# CMOSArray.net
KiCad netlist of a schematic drawn in EAGLE
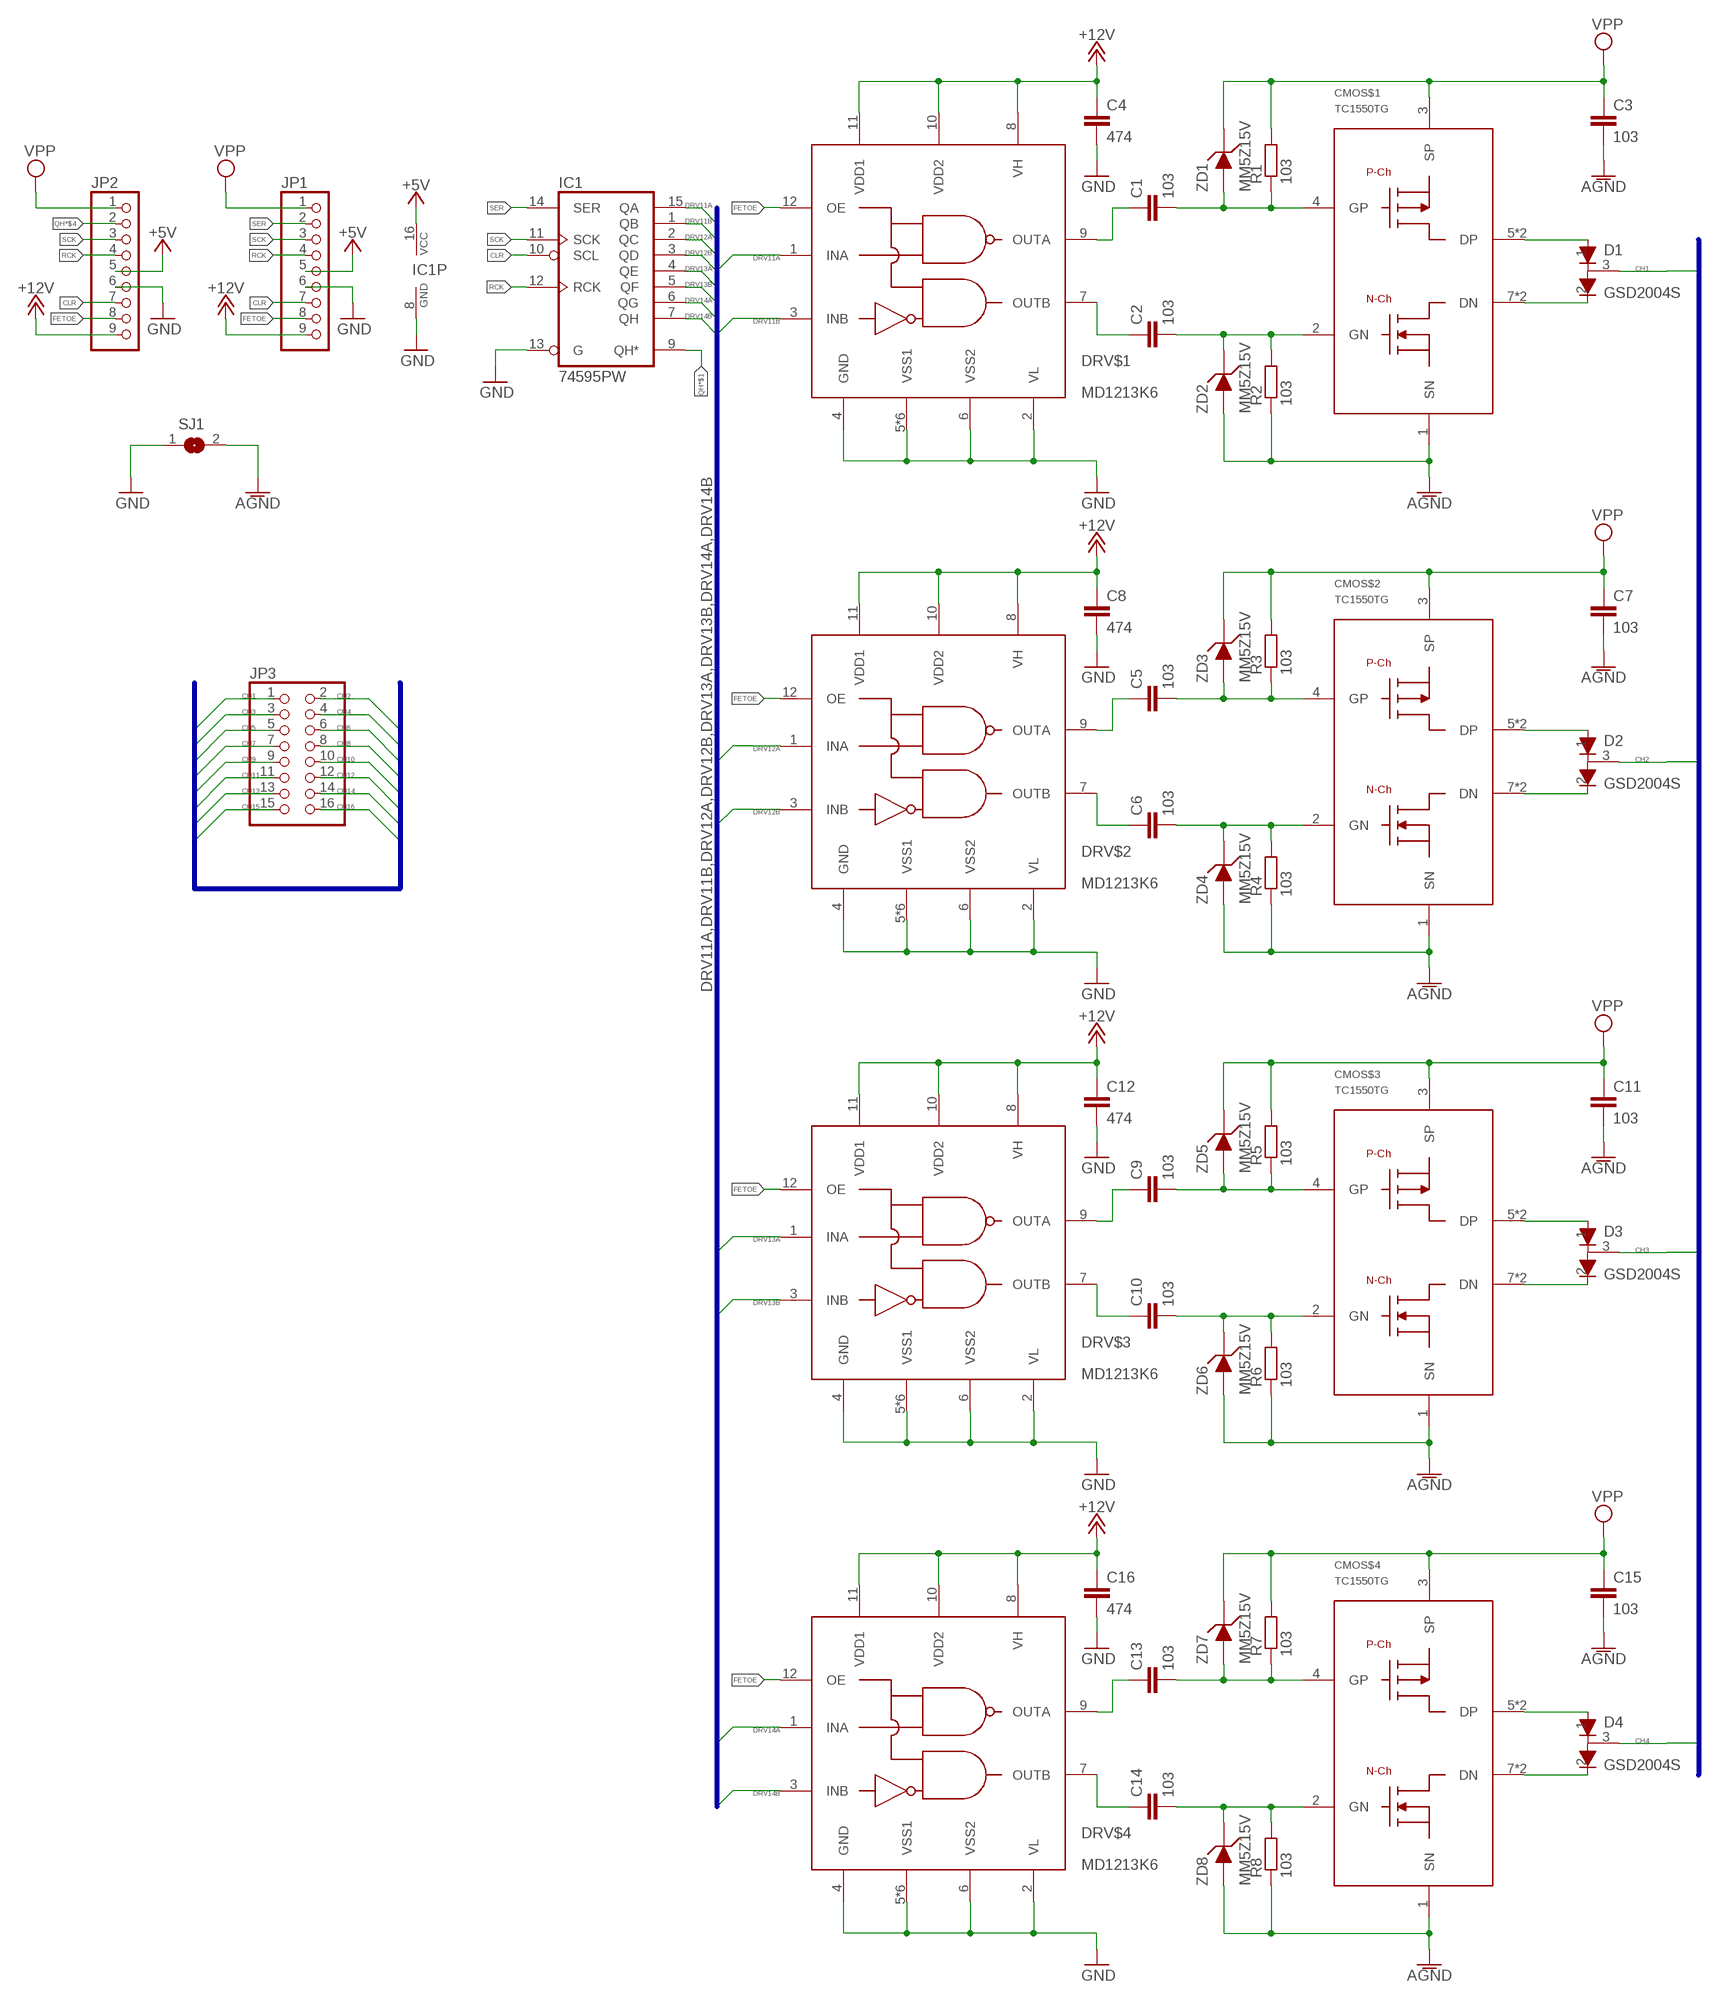
[diagram p0: schematic, sheet 1, part 1 of 3]
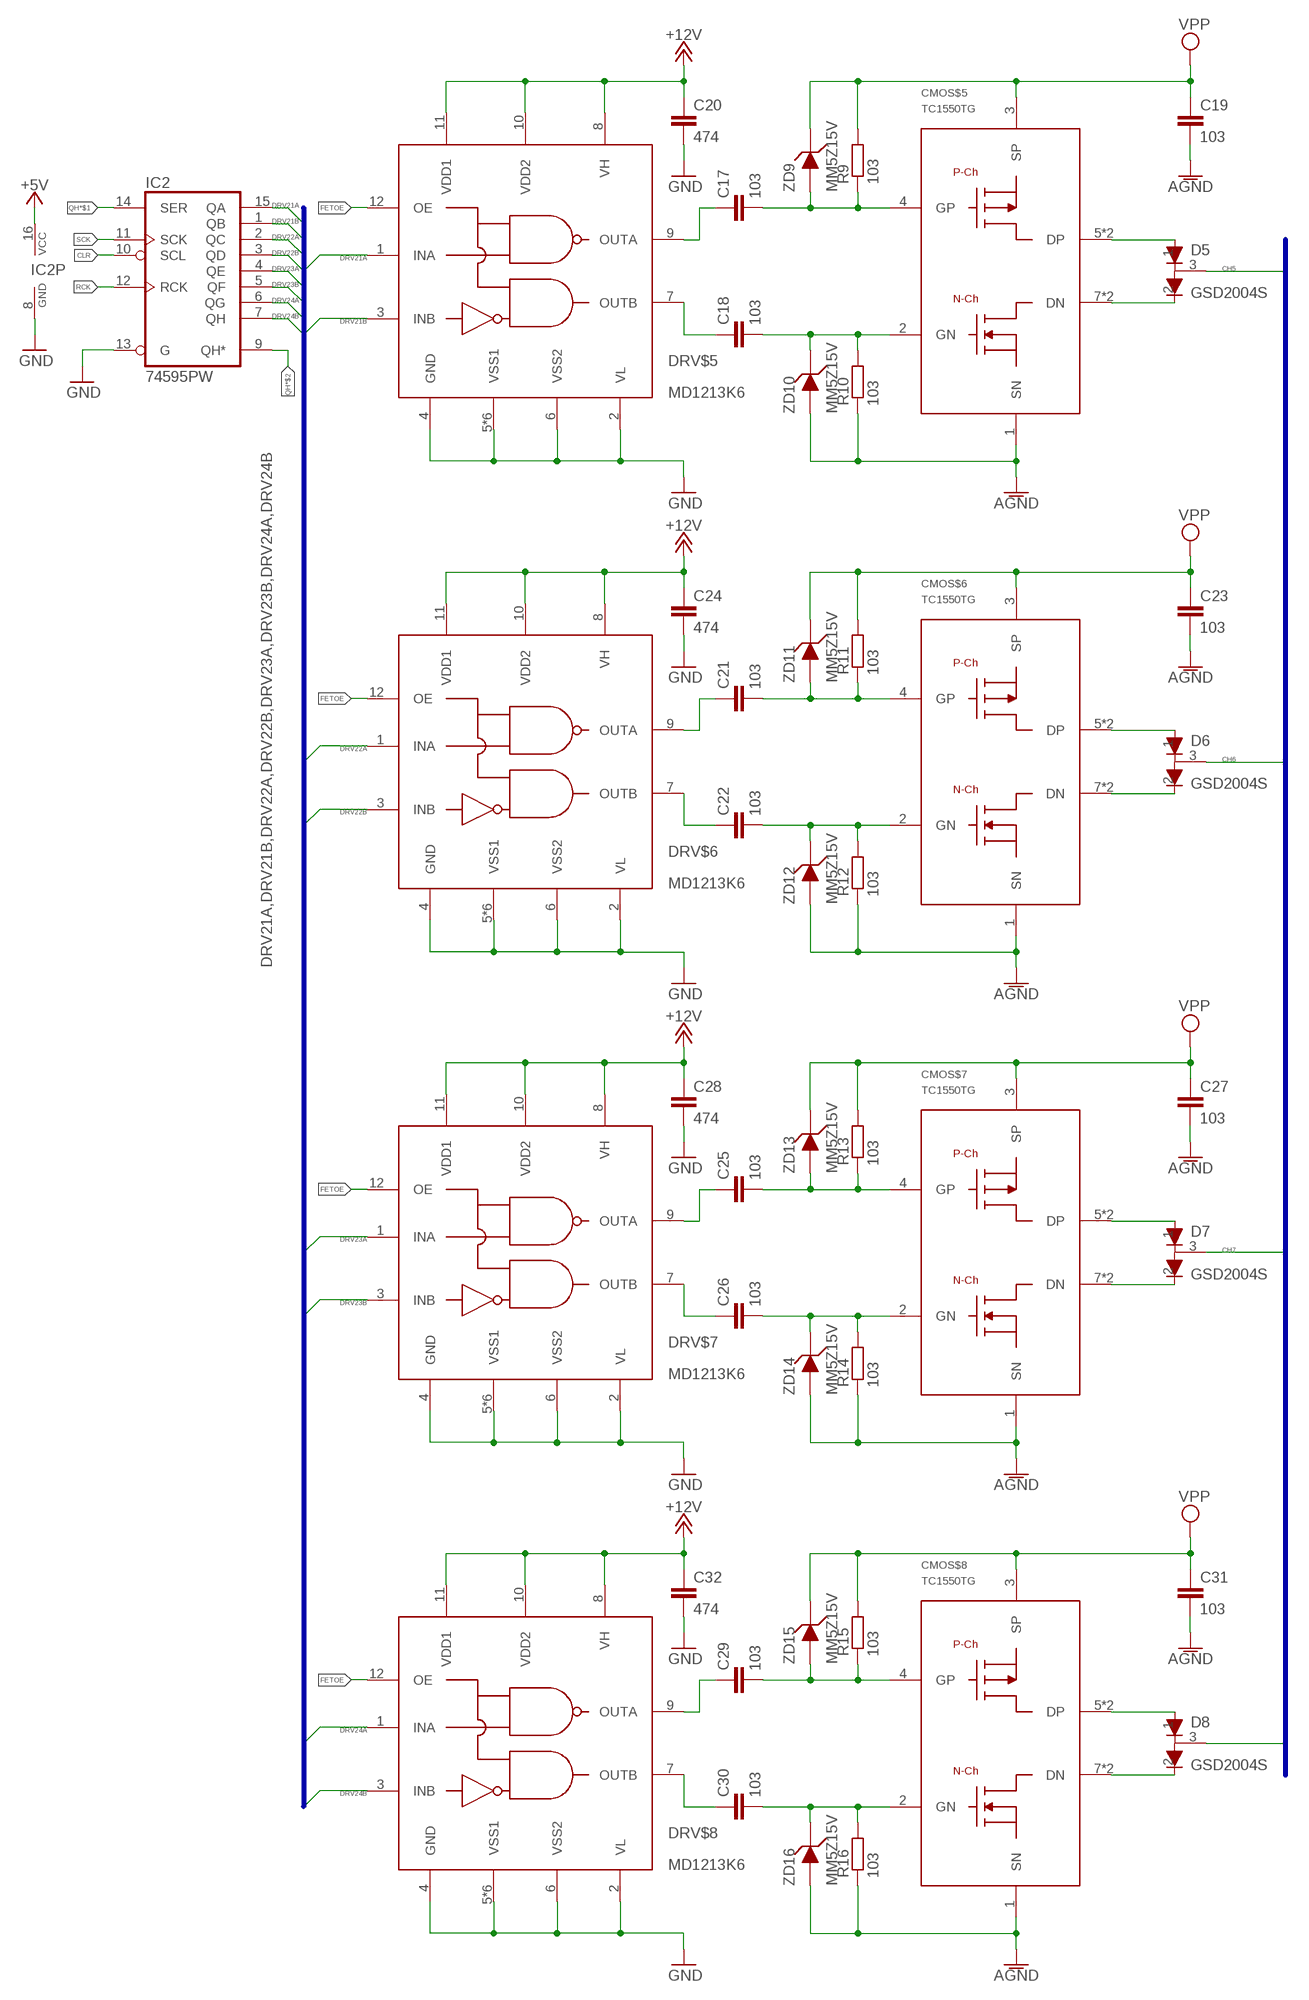
[diagram p1: schematic, sheet 1, part 2 of 3]
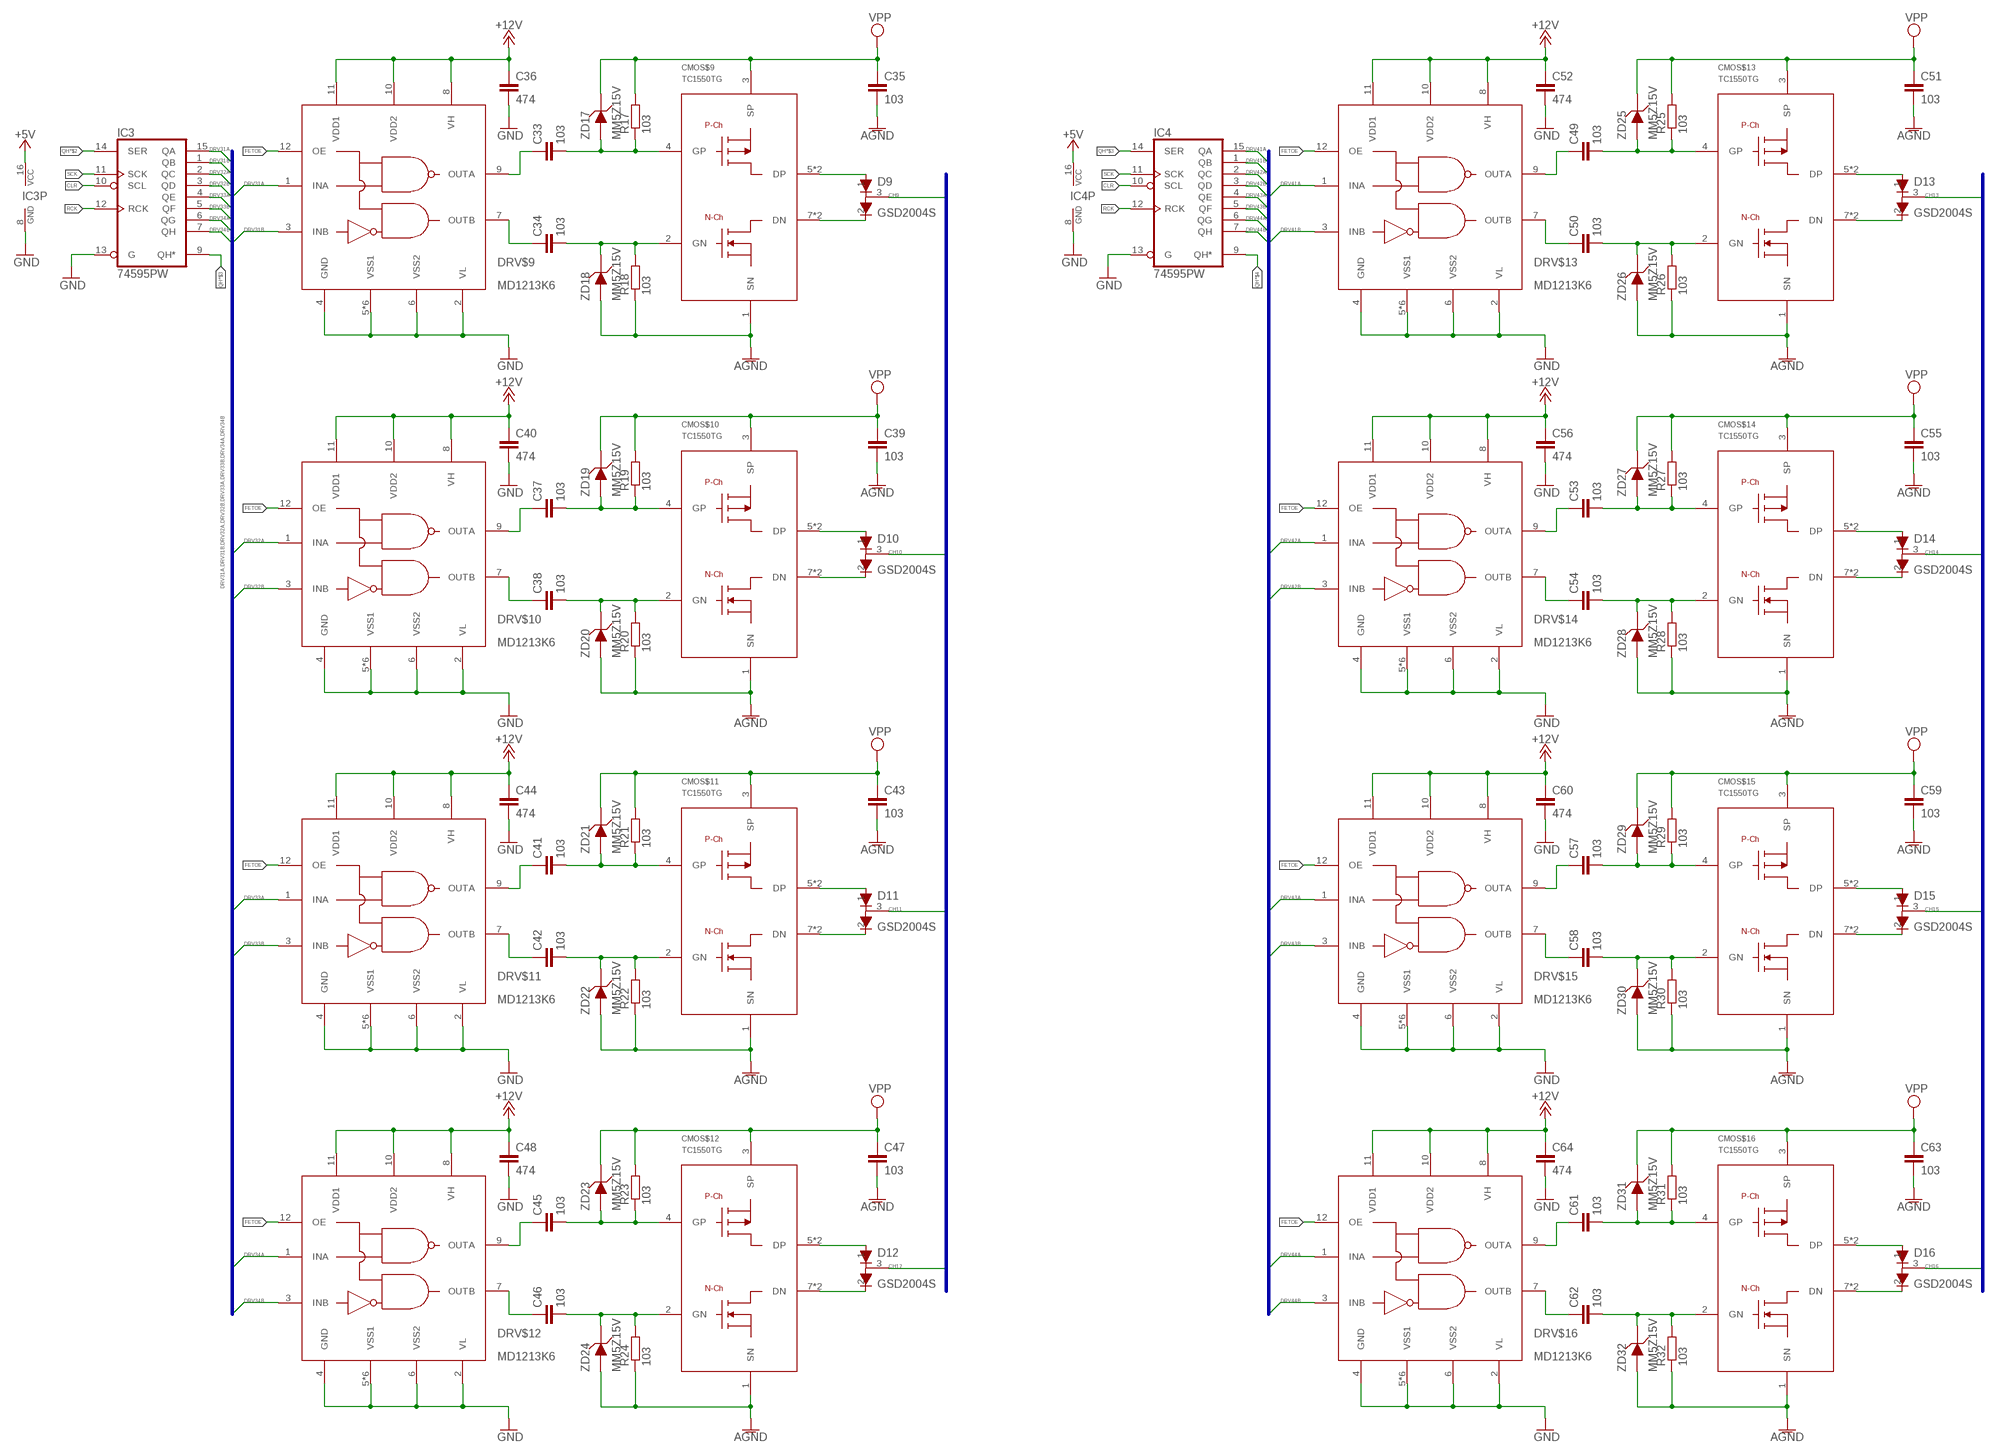
[diagram p2: schematic, sheet 1, part 3 of 3]

(export (version "E")
  (design (tool "Eeschema 10.0.6"))
  (components
    (comp (ref "C1")
      (value "103")
      (footprint "eagle-import:C3216")
      (libsource (lib "eagle-import") (part "C-EUC3216"))
    )
    (comp (ref "C2")
      (value "103")
      (footprint "eagle-import:C3216")
      (libsource (lib "eagle-import") (part "C-EUC3216"))
    )
    (comp (ref "C3")
      (value "103")
      (footprint "eagle-import:C3216")
      (libsource (lib "eagle-import") (part "C-EUC3216"))
    )
    (comp (ref "C4")
      (value "474")
      (footprint "eagle-import:C0402")
      (libsource (lib "eagle-import") (part "C-EUC0402"))
    )
    (comp (ref "C5")
      (value "103")
      (footprint "eagle-import:C3216")
      (libsource (lib "eagle-import") (part "C-EUC3216"))
    )
    (comp (ref "C6")
      (value "103")
      (footprint "eagle-import:C3216")
      (libsource (lib "eagle-import") (part "C-EUC3216"))
    )
    (comp (ref "C7")
      (value "103")
      (footprint "eagle-import:C3216")
      (libsource (lib "eagle-import") (part "C-EUC3216"))
    )
    (comp (ref "C8")
      (value "474")
      (footprint "eagle-import:C0402")
      (libsource (lib "eagle-import") (part "C-EUC0402"))
    )
    (comp (ref "C9")
      (value "103")
      (footprint "eagle-import:C3216")
      (libsource (lib "eagle-import") (part "C-EUC3216"))
    )
    (comp (ref "C10")
      (value "103")
      (footprint "eagle-import:C3216")
      (libsource (lib "eagle-import") (part "C-EUC3216"))
    )
    (comp (ref "C11")
      (value "103")
      (footprint "eagle-import:C3216")
      (libsource (lib "eagle-import") (part "C-EUC3216"))
    )
    (comp (ref "C12")
      (value "474")
      (footprint "eagle-import:C0402")
      (libsource (lib "eagle-import") (part "C-EUC0402"))
    )
    (comp (ref "C13")
      (value "103")
      (footprint "eagle-import:C3216")
      (libsource (lib "eagle-import") (part "C-EUC3216"))
    )
    (comp (ref "C14")
      (value "103")
      (footprint "eagle-import:C3216")
      (libsource (lib "eagle-import") (part "C-EUC3216"))
    )
    (comp (ref "C15")
      (value "103")
      (footprint "eagle-import:C3216")
      (libsource (lib "eagle-import") (part "C-EUC3216"))
    )
    (comp (ref "C16")
      (value "474")
      (footprint "eagle-import:C0402")
      (libsource (lib "eagle-import") (part "C-EUC0402"))
    )
    (comp (ref "C17")
      (value "103")
      (footprint "eagle-import:C3216")
      (libsource (lib "eagle-import") (part "C-EUC3216"))
    )
    (comp (ref "C18")
      (value "103")
      (footprint "eagle-import:C3216")
      (libsource (lib "eagle-import") (part "C-EUC3216"))
    )
    (comp (ref "C19")
      (value "103")
      (footprint "eagle-import:C3216")
      (libsource (lib "eagle-import") (part "C-EUC3216"))
    )
    (comp (ref "C20")
      (value "474")
      (footprint "eagle-import:C0402")
      (libsource (lib "eagle-import") (part "C-EUC0402"))
    )
    (comp (ref "C21")
      (value "103")
      (footprint "eagle-import:C3216")
      (libsource (lib "eagle-import") (part "C-EUC3216"))
    )
    (comp (ref "C22")
      (value "103")
      (footprint "eagle-import:C3216")
      (libsource (lib "eagle-import") (part "C-EUC3216"))
    )
    (comp (ref "C23")
      (value "103")
      (footprint "eagle-import:C3216")
      (libsource (lib "eagle-import") (part "C-EUC3216"))
    )
    (comp (ref "C24")
      (value "474")
      (footprint "eagle-import:C0402")
      (libsource (lib "eagle-import") (part "C-EUC0402"))
    )
    (comp (ref "C25")
      (value "103")
      (footprint "eagle-import:C3216")
      (libsource (lib "eagle-import") (part "C-EUC3216"))
    )
    (comp (ref "C26")
      (value "103")
      (footprint "eagle-import:C3216")
      (libsource (lib "eagle-import") (part "C-EUC3216"))
    )
    (comp (ref "C27")
      (value "103")
      (footprint "eagle-import:C3216")
      (libsource (lib "eagle-import") (part "C-EUC3216"))
    )
    (comp (ref "C28")
      (value "474")
      (footprint "eagle-import:C0402")
      (libsource (lib "eagle-import") (part "C-EUC0402"))
    )
    (comp (ref "C29")
      (value "103")
      (footprint "eagle-import:C3216")
      (libsource (lib "eagle-import") (part "C-EUC3216"))
    )
    (comp (ref "C30")
      (value "103")
      (footprint "eagle-import:C3216")
      (libsource (lib "eagle-import") (part "C-EUC3216"))
    )
    (comp (ref "C31")
      (value "103")
      (footprint "eagle-import:C3216")
      (libsource (lib "eagle-import") (part "C-EUC3216"))
    )
    (comp (ref "C32")
      (value "474")
      (footprint "eagle-import:C0402")
      (libsource (lib "eagle-import") (part "C-EUC0402"))
    )
    (comp (ref "C33")
      (value "103")
      (footprint "eagle-import:C3216")
      (libsource (lib "eagle-import") (part "C-EUC3216"))
    )
    (comp (ref "C34")
      (value "103")
      (footprint "eagle-import:C3216")
      (libsource (lib "eagle-import") (part "C-EUC3216"))
    )
    (comp (ref "C35")
      (value "103")
      (footprint "eagle-import:C3216")
      (libsource (lib "eagle-import") (part "C-EUC3216"))
    )
    (comp (ref "C36")
      (value "474")
      (footprint "eagle-import:C0402")
      (libsource (lib "eagle-import") (part "C-EUC0402"))
    )
    (comp (ref "C37")
      (value "103")
      (footprint "eagle-import:C3216")
      (libsource (lib "eagle-import") (part "C-EUC3216"))
    )
    (comp (ref "C38")
      (value "103")
      (footprint "eagle-import:C3216")
      (libsource (lib "eagle-import") (part "C-EUC3216"))
    )
    (comp (ref "C39")
      (value "103")
      (footprint "eagle-import:C3216")
      (libsource (lib "eagle-import") (part "C-EUC3216"))
    )
    (comp (ref "C40")
      (value "474")
      (footprint "eagle-import:C0402")
      (libsource (lib "eagle-import") (part "C-EUC0402"))
    )
    (comp (ref "C41")
      (value "103")
      (footprint "eagle-import:C3216")
      (libsource (lib "eagle-import") (part "C-EUC3216"))
    )
    (comp (ref "C42")
      (value "103")
      (footprint "eagle-import:C3216")
      (libsource (lib "eagle-import") (part "C-EUC3216"))
    )
    (comp (ref "C43")
      (value "103")
      (footprint "eagle-import:C3216")
      (libsource (lib "eagle-import") (part "C-EUC3216"))
    )
    (comp (ref "C44")
      (value "474")
      (footprint "eagle-import:C0402")
      (libsource (lib "eagle-import") (part "C-EUC0402"))
    )
    (comp (ref "C45")
      (value "103")
      (footprint "eagle-import:C3216")
      (libsource (lib "eagle-import") (part "C-EUC3216"))
    )
    (comp (ref "C46")
      (value "103")
      (footprint "eagle-import:C3216")
      (libsource (lib "eagle-import") (part "C-EUC3216"))
    )
    (comp (ref "C47")
      (value "103")
      (footprint "eagle-import:C3216")
      (libsource (lib "eagle-import") (part "C-EUC3216"))
    )
    (comp (ref "C48")
      (value "474")
      (footprint "eagle-import:C0402")
      (libsource (lib "eagle-import") (part "C-EUC0402"))
    )
    (comp (ref "C49")
      (value "103")
      (footprint "eagle-import:C3216")
      (libsource (lib "eagle-import") (part "C-EUC3216"))
    )
    (comp (ref "C50")
      (value "103")
      (footprint "eagle-import:C3216")
      (libsource (lib "eagle-import") (part "C-EUC3216"))
    )
    (comp (ref "C51")
      (value "103")
      (footprint "eagle-import:C3216")
      (libsource (lib "eagle-import") (part "C-EUC3216"))
    )
    (comp (ref "C52")
      (value "474")
      (footprint "eagle-import:C0402")
      (libsource (lib "eagle-import") (part "C-EUC0402"))
    )
    (comp (ref "C53")
      (value "103")
      (footprint "eagle-import:C3216")
      (libsource (lib "eagle-import") (part "C-EUC3216"))
    )
    (comp (ref "C54")
      (value "103")
      (footprint "eagle-import:C3216")
      (libsource (lib "eagle-import") (part "C-EUC3216"))
    )
    (comp (ref "C55")
      (value "103")
      (footprint "eagle-import:C3216")
      (libsource (lib "eagle-import") (part "C-EUC3216"))
    )
    (comp (ref "C56")
      (value "474")
      (footprint "eagle-import:C0402")
      (libsource (lib "eagle-import") (part "C-EUC0402"))
    )
    (comp (ref "C57")
      (value "103")
      (footprint "eagle-import:C3216")
      (libsource (lib "eagle-import") (part "C-EUC3216"))
    )
    (comp (ref "C58")
      (value "103")
      (footprint "eagle-import:C3216")
      (libsource (lib "eagle-import") (part "C-EUC3216"))
    )
    (comp (ref "C59")
      (value "103")
      (footprint "eagle-import:C3216")
      (libsource (lib "eagle-import") (part "C-EUC3216"))
    )
    (comp (ref "C60")
      (value "474")
      (footprint "eagle-import:C0402")
      (libsource (lib "eagle-import") (part "C-EUC0402"))
    )
    (comp (ref "C61")
      (value "103")
      (footprint "eagle-import:C3216")
      (libsource (lib "eagle-import") (part "C-EUC3216"))
    )
    (comp (ref "C62")
      (value "103")
      (footprint "eagle-import:C3216")
      (libsource (lib "eagle-import") (part "C-EUC3216"))
    )
    (comp (ref "C63")
      (value "103")
      (footprint "eagle-import:C3216")
      (libsource (lib "eagle-import") (part "C-EUC3216"))
    )
    (comp (ref "C64")
      (value "474")
      (footprint "eagle-import:C0402")
      (libsource (lib "eagle-import") (part "C-EUC0402"))
    )
    (comp (ref "CMOS$1")
      (value "TC1550TG")
      (footprint "eagle-import:SOIC-08LG")
      (libsource (lib "eagle-import") (part "TC1550TG"))
    )
    (comp (ref "CMOS$2")
      (value "TC1550TG")
      (footprint "eagle-import:SOIC-08LG")
      (libsource (lib "eagle-import") (part "TC1550TG"))
    )
    (comp (ref "CMOS$3")
      (value "TC1550TG")
      (footprint "eagle-import:SOIC-08LG")
      (libsource (lib "eagle-import") (part "TC1550TG"))
    )
    (comp (ref "CMOS$4")
      (value "TC1550TG")
      (footprint "eagle-import:SOIC-08LG")
      (libsource (lib "eagle-import") (part "TC1550TG"))
    )
    (comp (ref "CMOS$5")
      (value "TC1550TG")
      (footprint "eagle-import:SOIC-08LG")
      (libsource (lib "eagle-import") (part "TC1550TG"))
    )
    (comp (ref "CMOS$6")
      (value "TC1550TG")
      (footprint "eagle-import:SOIC-08LG")
      (libsource (lib "eagle-import") (part "TC1550TG"))
    )
    (comp (ref "CMOS$7")
      (value "TC1550TG")
      (footprint "eagle-import:SOIC-08LG")
      (libsource (lib "eagle-import") (part "TC1550TG"))
    )
    (comp (ref "CMOS$8")
      (value "TC1550TG")
      (footprint "eagle-import:SOIC-08LG")
      (libsource (lib "eagle-import") (part "TC1550TG"))
    )
    (comp (ref "CMOS$9")
      (value "TC1550TG")
      (footprint "eagle-import:SOIC-08LG")
      (libsource (lib "eagle-import") (part "TC1550TG"))
    )
    (comp (ref "CMOS$10")
      (value "TC1550TG")
      (footprint "eagle-import:SOIC-08LG")
      (libsource (lib "eagle-import") (part "TC1550TG"))
    )
    (comp (ref "CMOS$11")
      (value "TC1550TG")
      (footprint "eagle-import:SOIC-08LG")
      (libsource (lib "eagle-import") (part "TC1550TG"))
    )
    (comp (ref "CMOS$12")
      (value "TC1550TG")
      (footprint "eagle-import:SOIC-08LG")
      (libsource (lib "eagle-import") (part "TC1550TG"))
    )
    (comp (ref "CMOS$13")
      (value "TC1550TG")
      (footprint "eagle-import:SOIC-08LG")
      (libsource (lib "eagle-import") (part "TC1550TG"))
    )
    (comp (ref "CMOS$14")
      (value "TC1550TG")
      (footprint "eagle-import:SOIC-08LG")
      (libsource (lib "eagle-import") (part "TC1550TG"))
    )
    (comp (ref "CMOS$15")
      (value "TC1550TG")
      (footprint "eagle-import:SOIC-08LG")
      (libsource (lib "eagle-import") (part "TC1550TG"))
    )
    (comp (ref "CMOS$16")
      (value "TC1550TG")
      (footprint "eagle-import:SOIC-08LG")
      (libsource (lib "eagle-import") (part "TC1550TG"))
    )
    (comp (ref "D1")
      (value "GSD2004S")
      (footprint "eagle-import:SOT23")
      (libsource (lib "eagle-import") (part "GSD2004S"))
    )
    (comp (ref "D2")
      (value "GSD2004S")
      (footprint "eagle-import:SOT23")
      (libsource (lib "eagle-import") (part "GSD2004S"))
    )
    (comp (ref "D3")
      (value "GSD2004S")
      (footprint "eagle-import:SOT23")
      (libsource (lib "eagle-import") (part "GSD2004S"))
    )
    (comp (ref "D4")
      (value "GSD2004S")
      (footprint "eagle-import:SOT23")
      (libsource (lib "eagle-import") (part "GSD2004S"))
    )
    (comp (ref "D5")
      (value "GSD2004S")
      (footprint "eagle-import:SOT23")
      (libsource (lib "eagle-import") (part "GSD2004S"))
    )
    (comp (ref "D6")
      (value "GSD2004S")
      (footprint "eagle-import:SOT23")
      (libsource (lib "eagle-import") (part "GSD2004S"))
    )
    (comp (ref "D7")
      (value "GSD2004S")
      (footprint "eagle-import:SOT23")
      (libsource (lib "eagle-import") (part "GSD2004S"))
    )
    (comp (ref "D8")
      (value "GSD2004S")
      (footprint "eagle-import:SOT23")
      (libsource (lib "eagle-import") (part "GSD2004S"))
    )
    (comp (ref "D9")
      (value "GSD2004S")
      (footprint "eagle-import:SOT23")
      (libsource (lib "eagle-import") (part "GSD2004S"))
    )
    (comp (ref "D10")
      (value "GSD2004S")
      (footprint "eagle-import:SOT23")
      (libsource (lib "eagle-import") (part "GSD2004S"))
    )
    (comp (ref "D11")
      (value "GSD2004S")
      (footprint "eagle-import:SOT23")
      (libsource (lib "eagle-import") (part "GSD2004S"))
    )
    (comp (ref "D12")
      (value "GSD2004S")
      (footprint "eagle-import:SOT23")
      (libsource (lib "eagle-import") (part "GSD2004S"))
    )
    (comp (ref "D13")
      (value "GSD2004S")
      (footprint "eagle-import:SOT23")
      (libsource (lib "eagle-import") (part "GSD2004S"))
    )
    (comp (ref "D14")
      (value "GSD2004S")
      (footprint "eagle-import:SOT23")
      (libsource (lib "eagle-import") (part "GSD2004S"))
    )
    (comp (ref "D15")
      (value "GSD2004S")
      (footprint "eagle-import:SOT23")
      (libsource (lib "eagle-import") (part "GSD2004S"))
    )
    (comp (ref "D16")
      (value "GSD2004S")
      (footprint "eagle-import:SOT23")
      (libsource (lib "eagle-import") (part "GSD2004S"))
    )
    (comp (ref "DRV$1")
      (value "MD1213K6")
      (footprint "eagle-import:QFN12")
      (libsource (lib "eagle-import") (part "MD1213K6"))
    )
    (comp (ref "DRV$2")
      (value "MD1213K6")
      (footprint "eagle-import:QFN12")
      (libsource (lib "eagle-import") (part "MD1213K6"))
    )
    (comp (ref "DRV$3")
      (value "MD1213K6")
      (footprint "eagle-import:QFN12")
      (libsource (lib "eagle-import") (part "MD1213K6"))
    )
    (comp (ref "DRV$4")
      (value "MD1213K6")
      (footprint "eagle-import:QFN12")
      (libsource (lib "eagle-import") (part "MD1213K6"))
    )
    (comp (ref "DRV$5")
      (value "MD1213K6")
      (footprint "eagle-import:QFN12")
      (libsource (lib "eagle-import") (part "MD1213K6"))
    )
    (comp (ref "DRV$6")
      (value "MD1213K6")
      (footprint "eagle-import:QFN12")
      (libsource (lib "eagle-import") (part "MD1213K6"))
    )
    (comp (ref "DRV$7")
      (value "MD1213K6")
      (footprint "eagle-import:QFN12")
      (libsource (lib "eagle-import") (part "MD1213K6"))
    )
    (comp (ref "DRV$8")
      (value "MD1213K6")
      (footprint "eagle-import:QFN12")
      (libsource (lib "eagle-import") (part "MD1213K6"))
    )
    (comp (ref "DRV$9")
      (value "MD1213K6")
      (footprint "eagle-import:QFN12")
      (libsource (lib "eagle-import") (part "MD1213K6"))
    )
    (comp (ref "DRV$10")
      (value "MD1213K6")
      (footprint "eagle-import:QFN12")
      (libsource (lib "eagle-import") (part "MD1213K6"))
    )
    (comp (ref "DRV$11")
      (value "MD1213K6")
      (footprint "eagle-import:QFN12")
      (libsource (lib "eagle-import") (part "MD1213K6"))
    )
    (comp (ref "DRV$12")
      (value "MD1213K6")
      (footprint "eagle-import:QFN12")
      (libsource (lib "eagle-import") (part "MD1213K6"))
    )
    (comp (ref "DRV$13")
      (value "MD1213K6")
      (footprint "eagle-import:QFN12")
      (libsource (lib "eagle-import") (part "MD1213K6"))
    )
    (comp (ref "DRV$14")
      (value "MD1213K6")
      (footprint "eagle-import:QFN12")
      (libsource (lib "eagle-import") (part "MD1213K6"))
    )
    (comp (ref "DRV$15")
      (value "MD1213K6")
      (footprint "eagle-import:QFN12")
      (libsource (lib "eagle-import") (part "MD1213K6"))
    )
    (comp (ref "DRV$16")
      (value "MD1213K6")
      (footprint "eagle-import:QFN12")
      (libsource (lib "eagle-import") (part "MD1213K6"))
    )
    (comp (ref "IC1")
      (value "74595PW")
      (footprint "eagle-import:TTSOP16")
      (libsource (lib "eagle-import") (part "74595PW"))
    )
    (comp (ref "IC2")
      (value "74595PW")
      (footprint "eagle-import:TTSOP16")
      (libsource (lib "eagle-import") (part "74595PW"))
    )
    (comp (ref "IC3")
      (value "74595PW")
      (footprint "eagle-import:TTSOP16")
      (libsource (lib "eagle-import") (part "74595PW"))
    )
    (comp (ref "IC4")
      (value "74595PW")
      (footprint "eagle-import:TTSOP16")
      (libsource (lib "eagle-import") (part "74595PW"))
    )
    (comp (ref "JP1")
      (value "PINHD-1X9")
      (footprint "eagle-import:1X09")
      (libsource (lib "eagle-import") (part "PINHD-1X9"))
    )
    (comp (ref "JP2")
      (value "PINHD-1X9")
      (footprint "eagle-import:1X09")
      (libsource (lib "eagle-import") (part "PINHD-1X9"))
    )
    (comp (ref "JP3")
      (value "PINHD-2X8")
      (footprint "eagle-import:2X08")
      (libsource (lib "eagle-import") (part "PINHD-2X8"))
    )
    (comp (ref "R1")
      (value "103")
      (footprint "eagle-import:R0402")
      (libsource (lib "eagle-import") (part "R-EU_R0402"))
    )
    (comp (ref "R2")
      (value "103")
      (footprint "eagle-import:R0402")
      (libsource (lib "eagle-import") (part "R-EU_R0402"))
    )
    (comp (ref "R3")
      (value "103")
      (footprint "eagle-import:R0402")
      (libsource (lib "eagle-import") (part "R-EU_R0402"))
    )
    (comp (ref "R4")
      (value "103")
      (footprint "eagle-import:R0402")
      (libsource (lib "eagle-import") (part "R-EU_R0402"))
    )
    (comp (ref "R5")
      (value "103")
      (footprint "eagle-import:R0402")
      (libsource (lib "eagle-import") (part "R-EU_R0402"))
    )
    (comp (ref "R6")
      (value "103")
      (footprint "eagle-import:R0402")
      (libsource (lib "eagle-import") (part "R-EU_R0402"))
    )
    (comp (ref "R7")
      (value "103")
      (footprint "eagle-import:R0402")
      (libsource (lib "eagle-import") (part "R-EU_R0402"))
    )
    (comp (ref "R8")
      (value "103")
      (footprint "eagle-import:R0402")
      (libsource (lib "eagle-import") (part "R-EU_R0402"))
    )
    (comp (ref "R9")
      (value "103")
      (footprint "eagle-import:R0402")
      (libsource (lib "eagle-import") (part "R-EU_R0402"))
    )
    (comp (ref "R10")
      (value "103")
      (footprint "eagle-import:R0402")
      (libsource (lib "eagle-import") (part "R-EU_R0402"))
    )
    (comp (ref "R11")
      (value "103")
      (footprint "eagle-import:R0402")
      (libsource (lib "eagle-import") (part "R-EU_R0402"))
    )
    (comp (ref "R12")
      (value "103")
      (footprint "eagle-import:R0402")
      (libsource (lib "eagle-import") (part "R-EU_R0402"))
    )
    (comp (ref "R13")
      (value "103")
      (footprint "eagle-import:R0402")
      (libsource (lib "eagle-import") (part "R-EU_R0402"))
    )
    (comp (ref "R14")
      (value "103")
      (footprint "eagle-import:R0402")
      (libsource (lib "eagle-import") (part "R-EU_R0402"))
    )
    (comp (ref "R15")
      (value "103")
      (footprint "eagle-import:R0402")
      (libsource (lib "eagle-import") (part "R-EU_R0402"))
    )
    (comp (ref "R16")
      (value "103")
      (footprint "eagle-import:R0402")
      (libsource (lib "eagle-import") (part "R-EU_R0402"))
    )
    (comp (ref "R17")
      (value "103")
      (footprint "eagle-import:R0402")
      (libsource (lib "eagle-import") (part "R-EU_R0402"))
    )
    (comp (ref "R18")
      (value "103")
      (footprint "eagle-import:R0402")
      (libsource (lib "eagle-import") (part "R-EU_R0402"))
    )
    (comp (ref "R19")
      (value "103")
      (footprint "eagle-import:R0402")
      (libsource (lib "eagle-import") (part "R-EU_R0402"))
    )
    (comp (ref "R20")
      (value "103")
      (footprint "eagle-import:R0402")
      (libsource (lib "eagle-import") (part "R-EU_R0402"))
    )
    (comp (ref "R21")
      (value "103")
      (footprint "eagle-import:R0402")
      (libsource (lib "eagle-import") (part "R-EU_R0402"))
    )
    (comp (ref "R22")
      (value "103")
      (footprint "eagle-import:R0402")
      (libsource (lib "eagle-import") (part "R-EU_R0402"))
    )
    (comp (ref "R23")
      (value "103")
      (footprint "eagle-import:R0402")
      (libsource (lib "eagle-import") (part "R-EU_R0402"))
    )
    (comp (ref "R24")
      (value "103")
      (footprint "eagle-import:R0402")
      (libsource (lib "eagle-import") (part "R-EU_R0402"))
    )
    (comp (ref "R25")
      (value "103")
      (footprint "eagle-import:R0402")
      (libsource (lib "eagle-import") (part "R-EU_R0402"))
    )
    (comp (ref "R26")
      (value "103")
      (footprint "eagle-import:R0402")
      (libsource (lib "eagle-import") (part "R-EU_R0402"))
    )
    (comp (ref "R27")
      (value "103")
      (footprint "eagle-import:R0402")
      (libsource (lib "eagle-import") (part "R-EU_R0402"))
    )
    (comp (ref "R28")
      (value "103")
      (footprint "eagle-import:R0402")
      (libsource (lib "eagle-import") (part "R-EU_R0402"))
    )
    (comp (ref "R29")
      (value "103")
      (footprint "eagle-import:R0402")
      (libsource (lib "eagle-import") (part "R-EU_R0402"))
    )
    (comp (ref "R30")
      (value "103")
      (footprint "eagle-import:R0402")
      (libsource (lib "eagle-import") (part "R-EU_R0402"))
    )
    (comp (ref "R31")
      (value "103")
      (footprint "eagle-import:R0402")
      (libsource (lib "eagle-import") (part "R-EU_R0402"))
    )
    (comp (ref "R32")
      (value "103")
      (footprint "eagle-import:R0402")
      (libsource (lib "eagle-import") (part "R-EU_R0402"))
    )
    (comp (ref "SJ1") (value "SJ") (footprint "eagle-import:SJ") (libsource (lib "eagle-import") (part "SJ")))
    (comp (ref "ZD1")
      (value "MM5Z15V")
      (footprint "eagle-import:SOD523")
      (libsource (lib "eagle-import") (part "MM5Z15V"))
    )
    (comp (ref "ZD2")
      (value "MM5Z15V")
      (footprint "eagle-import:SOD523")
      (libsource (lib "eagle-import") (part "MM5Z15V"))
    )
    (comp (ref "ZD3")
      (value "MM5Z15V")
      (footprint "eagle-import:SOD523")
      (libsource (lib "eagle-import") (part "MM5Z15V"))
    )
    (comp (ref "ZD4")
      (value "MM5Z15V")
      (footprint "eagle-import:SOD523")
      (libsource (lib "eagle-import") (part "MM5Z15V"))
    )
    (comp (ref "ZD5")
      (value "MM5Z15V")
      (footprint "eagle-import:SOD523")
      (libsource (lib "eagle-import") (part "MM5Z15V"))
    )
    (comp (ref "ZD6")
      (value "MM5Z15V")
      (footprint "eagle-import:SOD523")
      (libsource (lib "eagle-import") (part "MM5Z15V"))
    )
    (comp (ref "ZD7")
      (value "MM5Z15V")
      (footprint "eagle-import:SOD523")
      (libsource (lib "eagle-import") (part "MM5Z15V"))
    )
    (comp (ref "ZD8")
      (value "MM5Z15V")
      (footprint "eagle-import:SOD523")
      (libsource (lib "eagle-import") (part "MM5Z15V"))
    )
    (comp (ref "ZD9")
      (value "MM5Z15V")
      (footprint "eagle-import:SOD523")
      (libsource (lib "eagle-import") (part "MM5Z15V"))
    )
    (comp (ref "ZD10")
      (value "MM5Z15V")
      (footprint "eagle-import:SOD523")
      (libsource (lib "eagle-import") (part "MM5Z15V"))
    )
    (comp (ref "ZD11")
      (value "MM5Z15V")
      (footprint "eagle-import:SOD523")
      (libsource (lib "eagle-import") (part "MM5Z15V"))
    )
    (comp (ref "ZD12")
      (value "MM5Z15V")
      (footprint "eagle-import:SOD523")
      (libsource (lib "eagle-import") (part "MM5Z15V"))
    )
    (comp (ref "ZD13")
      (value "MM5Z15V")
      (footprint "eagle-import:SOD523")
      (libsource (lib "eagle-import") (part "MM5Z15V"))
    )
    (comp (ref "ZD14")
      (value "MM5Z15V")
      (footprint "eagle-import:SOD523")
      (libsource (lib "eagle-import") (part "MM5Z15V"))
    )
    (comp (ref "ZD15")
      (value "MM5Z15V")
      (footprint "eagle-import:SOD523")
      (libsource (lib "eagle-import") (part "MM5Z15V"))
    )
    (comp (ref "ZD16")
      (value "MM5Z15V")
      (footprint "eagle-import:SOD523")
      (libsource (lib "eagle-import") (part "MM5Z15V"))
    )
    (comp (ref "ZD17")
      (value "MM5Z15V")
      (footprint "eagle-import:SOD523")
      (libsource (lib "eagle-import") (part "MM5Z15V"))
    )
    (comp (ref "ZD18")
      (value "MM5Z15V")
      (footprint "eagle-import:SOD523")
      (libsource (lib "eagle-import") (part "MM5Z15V"))
    )
    (comp (ref "ZD19")
      (value "MM5Z15V")
      (footprint "eagle-import:SOD523")
      (libsource (lib "eagle-import") (part "MM5Z15V"))
    )
    (comp (ref "ZD20")
      (value "MM5Z15V")
      (footprint "eagle-import:SOD523")
      (libsource (lib "eagle-import") (part "MM5Z15V"))
    )
    (comp (ref "ZD21")
      (value "MM5Z15V")
      (footprint "eagle-import:SOD523")
      (libsource (lib "eagle-import") (part "MM5Z15V"))
    )
    (comp (ref "ZD22")
      (value "MM5Z15V")
      (footprint "eagle-import:SOD523")
      (libsource (lib "eagle-import") (part "MM5Z15V"))
    )
    (comp (ref "ZD23")
      (value "MM5Z15V")
      (footprint "eagle-import:SOD523")
      (libsource (lib "eagle-import") (part "MM5Z15V"))
    )
    (comp (ref "ZD24")
      (value "MM5Z15V")
      (footprint "eagle-import:SOD523")
      (libsource (lib "eagle-import") (part "MM5Z15V"))
    )
    (comp (ref "ZD25")
      (value "MM5Z15V")
      (footprint "eagle-import:SOD523")
      (libsource (lib "eagle-import") (part "MM5Z15V"))
    )
    (comp (ref "ZD26")
      (value "MM5Z15V")
      (footprint "eagle-import:SOD523")
      (libsource (lib "eagle-import") (part "MM5Z15V"))
    )
    (comp (ref "ZD27")
      (value "MM5Z15V")
      (footprint "eagle-import:SOD523")
      (libsource (lib "eagle-import") (part "MM5Z15V"))
    )
    (comp (ref "ZD28")
      (value "MM5Z15V")
      (footprint "eagle-import:SOD523")
      (libsource (lib "eagle-import") (part "MM5Z15V"))
    )
    (comp (ref "ZD29")
      (value "MM5Z15V")
      (footprint "eagle-import:SOD523")
      (libsource (lib "eagle-import") (part "MM5Z15V"))
    )
    (comp (ref "ZD30")
      (value "MM5Z15V")
      (footprint "eagle-import:SOD523")
      (libsource (lib "eagle-import") (part "MM5Z15V"))
    )
    (comp (ref "ZD31")
      (value "MM5Z15V")
      (footprint "eagle-import:SOD523")
      (libsource (lib "eagle-import") (part "MM5Z15V"))
    )
    (comp (ref "ZD32")
      (value "MM5Z15V")
      (footprint "eagle-import:SOD523")
      (libsource (lib "eagle-import") (part "MM5Z15V"))
    )
  )
  (nets
    (net (code "1") (name "+5V") (class "Default")
      (node (ref "IC1") (pin "16") (pinfunction "VCC_16") (pintype "power_in"))
      (node (ref "IC2") (pin "16") (pinfunction "VCC_16") (pintype "power_in"))
      (node (ref "IC3") (pin "16") (pinfunction "VCC_16") (pintype "power_in"))
      (node (ref "IC4") (pin "16") (pinfunction "VCC_16") (pintype "power_in"))
      (node (ref "JP1") (pin "5") (pinfunction "5_5") (pintype "passive"))
      (node (ref "JP2") (pin "5") (pinfunction "5_5") (pintype "passive"))
    )
    (net (code "2") (name "+12V") (class "Default")
      (node (ref "C12") (pin "1") (pinfunction "1_1") (pintype "passive"))
      (node (ref "C16") (pin "1") (pinfunction "1_1") (pintype "passive"))
      (node (ref "C20") (pin "1") (pinfunction "1_1") (pintype "passive"))
      (node (ref "C24") (pin "1") (pinfunction "1_1") (pintype "passive"))
      (node (ref "C28") (pin "1") (pinfunction "1_1") (pintype "passive"))
      (node (ref "C32") (pin "1") (pinfunction "1_1") (pintype "passive"))
      (node (ref "C36") (pin "1") (pinfunction "1_1") (pintype "passive"))
      (node (ref "C4") (pin "1") (pinfunction "1_1") (pintype "passive"))
      (node (ref "C40") (pin "1") (pinfunction "1_1") (pintype "passive"))
      (node (ref "C44") (pin "1") (pinfunction "1_1") (pintype "passive"))
      (node (ref "C48") (pin "1") (pinfunction "1_1") (pintype "passive"))
      (node (ref "C52") (pin "1") (pinfunction "1_1") (pintype "passive"))
      (node (ref "C56") (pin "1") (pinfunction "1_1") (pintype "passive"))
      (node (ref "C60") (pin "1") (pinfunction "1_1") (pintype "passive"))
      (node (ref "C64") (pin "1") (pinfunction "1_1") (pintype "passive"))
      (node (ref "C8") (pin "1") (pinfunction "1_1") (pintype "passive"))
      (node (ref "DRV$1") (pin "10") (pinfunction "VDD2_10") (pintype "bidirectional"))
      (node (ref "DRV$1") (pin "11") (pinfunction "VDD1_11") (pintype "bidirectional"))
      (node (ref "DRV$1") (pin "8") (pinfunction "VH_8") (pintype "bidirectional"))
      (node (ref "DRV$10") (pin "10") (pinfunction "VDD2_10") (pintype "bidirectional"))
      (node (ref "DRV$10") (pin "11") (pinfunction "VDD1_11") (pintype "bidirectional"))
      (node (ref "DRV$10") (pin "8") (pinfunction "VH_8") (pintype "bidirectional"))
      (node (ref "DRV$11") (pin "10") (pinfunction "VDD2_10") (pintype "bidirectional"))
      (node (ref "DRV$11") (pin "11") (pinfunction "VDD1_11") (pintype "bidirectional"))
      (node (ref "DRV$11") (pin "8") (pinfunction "VH_8") (pintype "bidirectional"))
      (node (ref "DRV$12") (pin "10") (pinfunction "VDD2_10") (pintype "bidirectional"))
      (node (ref "DRV$12") (pin "11") (pinfunction "VDD1_11") (pintype "bidirectional"))
      (node (ref "DRV$12") (pin "8") (pinfunction "VH_8") (pintype "bidirectional"))
      (node (ref "DRV$13") (pin "10") (pinfunction "VDD2_10") (pintype "bidirectional"))
      (node (ref "DRV$13") (pin "11") (pinfunction "VDD1_11") (pintype "bidirectional"))
      (node (ref "DRV$13") (pin "8") (pinfunction "VH_8") (pintype "bidirectional"))
      (node (ref "DRV$14") (pin "10") (pinfunction "VDD2_10") (pintype "bidirectional"))
      (node (ref "DRV$14") (pin "11") (pinfunction "VDD1_11") (pintype "bidirectional"))
      (node (ref "DRV$14") (pin "8") (pinfunction "VH_8") (pintype "bidirectional"))
      (node (ref "DRV$15") (pin "10") (pinfunction "VDD2_10") (pintype "bidirectional"))
      (node (ref "DRV$15") (pin "11") (pinfunction "VDD1_11") (pintype "bidirectional"))
      (node (ref "DRV$15") (pin "8") (pinfunction "VH_8") (pintype "bidirectional"))
      (node (ref "DRV$16") (pin "10") (pinfunction "VDD2_10") (pintype "bidirectional"))
      (node (ref "DRV$16") (pin "11") (pinfunction "VDD1_11") (pintype "bidirectional"))
      (node (ref "DRV$16") (pin "8") (pinfunction "VH_8") (pintype "bidirectional"))
      (node (ref "DRV$2") (pin "10") (pinfunction "VDD2_10") (pintype "bidirectional"))
      (node (ref "DRV$2") (pin "11") (pinfunction "VDD1_11") (pintype "bidirectional"))
      (node (ref "DRV$2") (pin "8") (pinfunction "VH_8") (pintype "bidirectional"))
      (node (ref "DRV$3") (pin "10") (pinfunction "VDD2_10") (pintype "bidirectional"))
      (node (ref "DRV$3") (pin "11") (pinfunction "VDD1_11") (pintype "bidirectional"))
      (node (ref "DRV$3") (pin "8") (pinfunction "VH_8") (pintype "bidirectional"))
      (node (ref "DRV$4") (pin "10") (pinfunction "VDD2_10") (pintype "bidirectional"))
      (node (ref "DRV$4") (pin "11") (pinfunction "VDD1_11") (pintype "bidirectional"))
      (node (ref "DRV$4") (pin "8") (pinfunction "VH_8") (pintype "bidirectional"))
      (node (ref "DRV$5") (pin "10") (pinfunction "VDD2_10") (pintype "bidirectional"))
      (node (ref "DRV$5") (pin "11") (pinfunction "VDD1_11") (pintype "bidirectional"))
      (node (ref "DRV$5") (pin "8") (pinfunction "VH_8") (pintype "bidirectional"))
      (node (ref "DRV$6") (pin "10") (pinfunction "VDD2_10") (pintype "bidirectional"))
      (node (ref "DRV$6") (pin "11") (pinfunction "VDD1_11") (pintype "bidirectional"))
      (node (ref "DRV$6") (pin "8") (pinfunction "VH_8") (pintype "bidirectional"))
      (node (ref "DRV$7") (pin "10") (pinfunction "VDD2_10") (pintype "bidirectional"))
      (node (ref "DRV$7") (pin "11") (pinfunction "VDD1_11") (pintype "bidirectional"))
      (node (ref "DRV$7") (pin "8") (pinfunction "VH_8") (pintype "bidirectional"))
      (node (ref "DRV$8") (pin "10") (pinfunction "VDD2_10") (pintype "bidirectional"))
      (node (ref "DRV$8") (pin "11") (pinfunction "VDD1_11") (pintype "bidirectional"))
      (node (ref "DRV$8") (pin "8") (pinfunction "VH_8") (pintype "bidirectional"))
      (node (ref "DRV$9") (pin "10") (pinfunction "VDD2_10") (pintype "bidirectional"))
      (node (ref "DRV$9") (pin "11") (pinfunction "VDD1_11") (pintype "bidirectional"))
      (node (ref "DRV$9") (pin "8") (pinfunction "VH_8") (pintype "bidirectional"))
      (node (ref "JP1") (pin "9") (pinfunction "9_9") (pintype "passive"))
      (node (ref "JP2") (pin "9") (pinfunction "9_9") (pintype "passive"))
    )
    (net (code "3") (name "/CH1") (class "Default")
      (node (ref "D1") (pin "3") (pinfunction "P$3_3") (pintype "passive"))
      (node (ref "JP3") (pin "1") (pinfunction "1_1") (pintype "passive"))
    )
    (net (code "4") (name "/CH2") (class "Default")
      (node (ref "D2") (pin "3") (pinfunction "P$3_3") (pintype "passive"))
      (node (ref "JP3") (pin "2") (pinfunction "2_2") (pintype "passive"))
    )
    (net (code "5") (name "/CH3") (class "Default")
      (node (ref "D3") (pin "3") (pinfunction "P$3_3") (pintype "passive"))
      (node (ref "JP3") (pin "3") (pinfunction "3_3") (pintype "passive"))
    )
    (net (code "6") (name "/CH4") (class "Default")
      (node (ref "D4") (pin "3") (pinfunction "P$3_3") (pintype "passive"))
      (node (ref "JP3") (pin "4") (pinfunction "4_4") (pintype "passive"))
    )
    (net (code "7") (name "/CH5") (class "Default")
      (node (ref "D5") (pin "3") (pinfunction "P$3_3") (pintype "passive"))
      (node (ref "JP3") (pin "5") (pinfunction "5_5") (pintype "passive"))
    )
    (net (code "8") (name "/CH6") (class "Default")
      (node (ref "D6") (pin "3") (pinfunction "P$3_3") (pintype "passive"))
      (node (ref "JP3") (pin "6") (pinfunction "6_6") (pintype "passive"))
    )
    (net (code "9") (name "/CH7") (class "Default")
      (node (ref "D7") (pin "3") (pinfunction "P$3_3") (pintype "passive"))
      (node (ref "JP3") (pin "7") (pinfunction "7_7") (pintype "passive"))
    )
    (net (code "10") (name "/CH8") (class "Default")
      (node (ref "D8") (pin "3") (pinfunction "P$3_3") (pintype "passive"))
      (node (ref "JP3") (pin "8") (pinfunction "8_8") (pintype "passive"))
    )
    (net (code "11") (name "/CH9") (class "Default")
      (node (ref "D9") (pin "3") (pinfunction "P$3_3") (pintype "passive"))
      (node (ref "JP3") (pin "9") (pinfunction "9_9") (pintype "passive"))
    )
    (net (code "12") (name "/CH10") (class "Default")
      (node (ref "D10") (pin "3") (pinfunction "P$3_3") (pintype "passive"))
      (node (ref "JP3") (pin "10") (pinfunction "10_10") (pintype "passive"))
    )
    (net (code "13") (name "/CH11") (class "Default")
      (node (ref "D11") (pin "3") (pinfunction "P$3_3") (pintype "passive"))
      (node (ref "JP3") (pin "11") (pinfunction "11_11") (pintype "passive"))
    )
    (net (code "14") (name "/CH12") (class "Default")
      (node (ref "D12") (pin "3") (pinfunction "P$3_3") (pintype "passive"))
      (node (ref "JP3") (pin "12") (pinfunction "12_12") (pintype "passive"))
    )
    (net (code "15") (name "/CH13") (class "Default")
      (node (ref "D13") (pin "3") (pinfunction "P$3_3") (pintype "passive"))
      (node (ref "JP3") (pin "13") (pinfunction "13_13") (pintype "passive"))
    )
    (net (code "16") (name "/CH14") (class "Default")
      (node (ref "D14") (pin "3") (pinfunction "P$3_3") (pintype "passive"))
      (node (ref "JP3") (pin "14") (pinfunction "14_14") (pintype "passive"))
    )
    (net (code "17") (name "/CH15") (class "Default")
      (node (ref "D15") (pin "3") (pinfunction "P$3_3") (pintype "passive"))
      (node (ref "JP3") (pin "15") (pinfunction "15_15") (pintype "passive"))
    )
    (net (code "18") (name "/CH16") (class "Default")
      (node (ref "D16") (pin "3") (pinfunction "P$3_3") (pintype "passive"))
      (node (ref "JP3") (pin "16") (pinfunction "16_16") (pintype "passive"))
    )
    (net (code "19") (name "/DRV11A") (class "Default")
      (node (ref "DRV$1") (pin "1") (pinfunction "INA_1") (pintype "bidirectional"))
      (node (ref "IC1") (pin "15") (pinfunction "QA_15") (pintype "tri_state"))
    )
    (net (code "20") (name "/DRV11B") (class "Default")
      (node (ref "DRV$1") (pin "3") (pinfunction "INB_3") (pintype "bidirectional"))
      (node (ref "IC1") (pin "1") (pinfunction "QB_1") (pintype "tri_state"))
    )
    (net (code "21") (name "/DRV12A") (class "Default")
      (node (ref "DRV$2") (pin "1") (pinfunction "INA_1") (pintype "bidirectional"))
      (node (ref "IC1") (pin "2") (pinfunction "QC_2") (pintype "tri_state"))
    )
    (net (code "22") (name "/DRV12B") (class "Default")
      (node (ref "DRV$2") (pin "3") (pinfunction "INB_3") (pintype "bidirectional"))
      (node (ref "IC1") (pin "3") (pinfunction "QD_3") (pintype "tri_state"))
    )
    (net (code "23") (name "/DRV13A") (class "Default")
      (node (ref "DRV$3") (pin "1") (pinfunction "INA_1") (pintype "bidirectional"))
      (node (ref "IC1") (pin "4") (pinfunction "QE_4") (pintype "tri_state"))
    )
    (net (code "24") (name "/DRV13B") (class "Default")
      (node (ref "DRV$3") (pin "3") (pinfunction "INB_3") (pintype "bidirectional"))
      (node (ref "IC1") (pin "5") (pinfunction "QF_5") (pintype "tri_state"))
    )
    (net (code "25") (name "/DRV14A") (class "Default")
      (node (ref "DRV$4") (pin "1") (pinfunction "INA_1") (pintype "bidirectional"))
      (node (ref "IC1") (pin "6") (pinfunction "QG_6") (pintype "tri_state"))
    )
    (net (code "26") (name "/DRV14B") (class "Default")
      (node (ref "DRV$4") (pin "3") (pinfunction "INB_3") (pintype "bidirectional"))
      (node (ref "IC1") (pin "7") (pinfunction "QH_7") (pintype "tri_state"))
    )
    (net (code "27") (name "/DRV21A") (class "Default")
      (node (ref "DRV$5") (pin "1") (pinfunction "INA_1") (pintype "bidirectional"))
      (node (ref "IC2") (pin "15") (pinfunction "QA_15") (pintype "tri_state"))
    )
    (net (code "28") (name "/DRV21B") (class "Default")
      (node (ref "DRV$5") (pin "3") (pinfunction "INB_3") (pintype "bidirectional"))
      (node (ref "IC2") (pin "1") (pinfunction "QB_1") (pintype "tri_state"))
    )
    (net (code "29") (name "/DRV22A") (class "Default")
      (node (ref "DRV$6") (pin "1") (pinfunction "INA_1") (pintype "bidirectional"))
      (node (ref "IC2") (pin "2") (pinfunction "QC_2") (pintype "tri_state"))
    )
    (net (code "30") (name "/DRV22B") (class "Default")
      (node (ref "DRV$6") (pin "3") (pinfunction "INB_3") (pintype "bidirectional"))
      (node (ref "IC2") (pin "3") (pinfunction "QD_3") (pintype "tri_state"))
    )
    (net (code "31") (name "/DRV23A") (class "Default")
      (node (ref "DRV$7") (pin "1") (pinfunction "INA_1") (pintype "bidirectional"))
      (node (ref "IC2") (pin "4") (pinfunction "QE_4") (pintype "tri_state"))
    )
    (net (code "32") (name "/DRV23B") (class "Default")
      (node (ref "DRV$7") (pin "3") (pinfunction "INB_3") (pintype "bidirectional"))
      (node (ref "IC2") (pin "5") (pinfunction "QF_5") (pintype "tri_state"))
    )
    (net (code "33") (name "/DRV24A") (class "Default")
      (node (ref "DRV$8") (pin "1") (pinfunction "INA_1") (pintype "bidirectional"))
      (node (ref "IC2") (pin "6") (pinfunction "QG_6") (pintype "tri_state"))
    )
    (net (code "34") (name "/DRV24B") (class "Default")
      (node (ref "DRV$8") (pin "3") (pinfunction "INB_3") (pintype "bidirectional"))
      (node (ref "IC2") (pin "7") (pinfunction "QH_7") (pintype "tri_state"))
    )
    (net (code "35") (name "/DRV31A") (class "Default")
      (node (ref "DRV$9") (pin "1") (pinfunction "INA_1") (pintype "bidirectional"))
      (node (ref "IC3") (pin "15") (pinfunction "QA_15") (pintype "tri_state"))
    )
    (net (code "36") (name "/DRV31B") (class "Default")
      (node (ref "DRV$9") (pin "3") (pinfunction "INB_3") (pintype "bidirectional"))
      (node (ref "IC3") (pin "1") (pinfunction "QB_1") (pintype "tri_state"))
    )
    (net (code "37") (name "/DRV32A") (class "Default")
      (node (ref "DRV$10") (pin "1") (pinfunction "INA_1") (pintype "bidirectional"))
      (node (ref "IC3") (pin "2") (pinfunction "QC_2") (pintype "tri_state"))
    )
    (net (code "38") (name "/DRV32B") (class "Default")
      (node (ref "DRV$10") (pin "3") (pinfunction "INB_3") (pintype "bidirectional"))
      (node (ref "IC3") (pin "3") (pinfunction "QD_3") (pintype "tri_state"))
    )
    (net (code "39") (name "/DRV33A") (class "Default")
      (node (ref "DRV$11") (pin "1") (pinfunction "INA_1") (pintype "bidirectional"))
      (node (ref "IC3") (pin "4") (pinfunction "QE_4") (pintype "tri_state"))
    )
    (net (code "40") (name "/DRV33B") (class "Default")
      (node (ref "DRV$11") (pin "3") (pinfunction "INB_3") (pintype "bidirectional"))
      (node (ref "IC3") (pin "5") (pinfunction "QF_5") (pintype "tri_state"))
    )
    (net (code "41") (name "/DRV34A") (class "Default")
      (node (ref "DRV$12") (pin "1") (pinfunction "INA_1") (pintype "bidirectional"))
      (node (ref "IC3") (pin "6") (pinfunction "QG_6") (pintype "tri_state"))
    )
    (net (code "42") (name "/DRV34B") (class "Default")
      (node (ref "DRV$12") (pin "3") (pinfunction "INB_3") (pintype "bidirectional"))
      (node (ref "IC3") (pin "7") (pinfunction "QH_7") (pintype "tri_state"))
    )
    (net (code "43") (name "/DRV41A") (class "Default")
      (node (ref "DRV$13") (pin "1") (pinfunction "INA_1") (pintype "bidirectional"))
      (node (ref "IC4") (pin "15") (pinfunction "QA_15") (pintype "tri_state"))
    )
    (net (code "44") (name "/DRV41B") (class "Default")
      (node (ref "DRV$13") (pin "3") (pinfunction "INB_3") (pintype "bidirectional"))
      (node (ref "IC4") (pin "1") (pinfunction "QB_1") (pintype "tri_state"))
    )
    (net (code "45") (name "/DRV42A") (class "Default")
      (node (ref "DRV$14") (pin "1") (pinfunction "INA_1") (pintype "bidirectional"))
      (node (ref "IC4") (pin "2") (pinfunction "QC_2") (pintype "tri_state"))
    )
    (net (code "46") (name "/DRV42B") (class "Default")
      (node (ref "DRV$14") (pin "3") (pinfunction "INB_3") (pintype "bidirectional"))
      (node (ref "IC4") (pin "3") (pinfunction "QD_3") (pintype "tri_state"))
    )
    (net (code "47") (name "/DRV43A") (class "Default")
      (node (ref "DRV$15") (pin "1") (pinfunction "INA_1") (pintype "bidirectional"))
      (node (ref "IC4") (pin "4") (pinfunction "QE_4") (pintype "tri_state"))
    )
    (net (code "48") (name "/DRV43B") (class "Default")
      (node (ref "DRV$15") (pin "3") (pinfunction "INB_3") (pintype "bidirectional"))
      (node (ref "IC4") (pin "5") (pinfunction "QF_5") (pintype "tri_state"))
    )
    (net (code "49") (name "/DRV44A") (class "Default")
      (node (ref "DRV$16") (pin "1") (pinfunction "INA_1") (pintype "bidirectional"))
      (node (ref "IC4") (pin "6") (pinfunction "QG_6") (pintype "tri_state"))
    )
    (net (code "50") (name "/DRV44B") (class "Default")
      (node (ref "DRV$16") (pin "3") (pinfunction "INB_3") (pintype "bidirectional"))
      (node (ref "IC4") (pin "7") (pinfunction "QH_7") (pintype "tri_state"))
    )
    (net (code "54") (name "AGND") (class "Default")
      (node (ref "C11") (pin "2") (pinfunction "2_2") (pintype "passive"))
      (node (ref "C15") (pin "2") (pinfunction "2_2") (pintype "passive"))
      (node (ref "C19") (pin "2") (pinfunction "2_2") (pintype "passive"))
      (node (ref "C23") (pin "2") (pinfunction "2_2") (pintype "passive"))
      (node (ref "C27") (pin "2") (pinfunction "2_2") (pintype "passive"))
      (node (ref "C3") (pin "2") (pinfunction "2_2") (pintype "passive"))
      (node (ref "C31") (pin "2") (pinfunction "2_2") (pintype "passive"))
      (node (ref "C35") (pin "2") (pinfunction "2_2") (pintype "passive"))
      (node (ref "C39") (pin "2") (pinfunction "2_2") (pintype "passive"))
      (node (ref "C43") (pin "2") (pinfunction "2_2") (pintype "passive"))
      (node (ref "C47") (pin "2") (pinfunction "2_2") (pintype "passive"))
      (node (ref "C51") (pin "2") (pinfunction "2_2") (pintype "passive"))
      (node (ref "C55") (pin "2") (pinfunction "2_2") (pintype "passive"))
      (node (ref "C59") (pin "2") (pinfunction "2_2") (pintype "passive"))
      (node (ref "C63") (pin "2") (pinfunction "2_2") (pintype "passive"))
      (node (ref "C7") (pin "2") (pinfunction "2_2") (pintype "passive"))
      (node (ref "CMOS$1") (pin "1") (pinfunction "SN_1") (pintype "bidirectional"))
      (node (ref "CMOS$10") (pin "1") (pinfunction "SN_1") (pintype "bidirectional"))
      (node (ref "CMOS$11") (pin "1") (pinfunction "SN_1") (pintype "bidirectional"))
      (node (ref "CMOS$12") (pin "1") (pinfunction "SN_1") (pintype "bidirectional"))
      (node (ref "CMOS$13") (pin "1") (pinfunction "SN_1") (pintype "bidirectional"))
      (node (ref "CMOS$14") (pin "1") (pinfunction "SN_1") (pintype "bidirectional"))
      (node (ref "CMOS$15") (pin "1") (pinfunction "SN_1") (pintype "bidirectional"))
      (node (ref "CMOS$16") (pin "1") (pinfunction "SN_1") (pintype "bidirectional"))
      (node (ref "CMOS$2") (pin "1") (pinfunction "SN_1") (pintype "bidirectional"))
      (node (ref "CMOS$3") (pin "1") (pinfunction "SN_1") (pintype "bidirectional"))
      (node (ref "CMOS$4") (pin "1") (pinfunction "SN_1") (pintype "bidirectional"))
      (node (ref "CMOS$5") (pin "1") (pinfunction "SN_1") (pintype "bidirectional"))
      (node (ref "CMOS$6") (pin "1") (pinfunction "SN_1") (pintype "bidirectional"))
      (node (ref "CMOS$7") (pin "1") (pinfunction "SN_1") (pintype "bidirectional"))
      (node (ref "CMOS$8") (pin "1") (pinfunction "SN_1") (pintype "bidirectional"))
      (node (ref "CMOS$9") (pin "1") (pinfunction "SN_1") (pintype "bidirectional"))
      (node (ref "R10") (pin "1") (pinfunction "1_1") (pintype "passive"))
      (node (ref "R12") (pin "1") (pinfunction "1_1") (pintype "passive"))
      (node (ref "R14") (pin "1") (pinfunction "1_1") (pintype "passive"))
      (node (ref "R16") (pin "1") (pinfunction "1_1") (pintype "passive"))
      (node (ref "R18") (pin "1") (pinfunction "1_1") (pintype "passive"))
      (node (ref "R2") (pin "1") (pinfunction "1_1") (pintype "passive"))
      (node (ref "R20") (pin "1") (pinfunction "1_1") (pintype "passive"))
      (node (ref "R22") (pin "1") (pinfunction "1_1") (pintype "passive"))
      (node (ref "R24") (pin "1") (pinfunction "1_1") (pintype "passive"))
      (node (ref "R26") (pin "1") (pinfunction "1_1") (pintype "passive"))
      (node (ref "R28") (pin "1") (pinfunction "1_1") (pintype "passive"))
      (node (ref "R30") (pin "1") (pinfunction "1_1") (pintype "passive"))
      (node (ref "R32") (pin "1") (pinfunction "1_1") (pintype "passive"))
      (node (ref "R4") (pin "1") (pinfunction "1_1") (pintype "passive"))
      (node (ref "R6") (pin "1") (pinfunction "1_1") (pintype "passive"))
      (node (ref "R8") (pin "1") (pinfunction "1_1") (pintype "passive"))
      (node (ref "SJ1") (pin "2") (pinfunction "2_2") (pintype "passive"))
      (node (ref "ZD10") (pin "P$2") (pinfunction "P$1_P$2") (pintype "passive"))
      (node (ref "ZD12") (pin "P$2") (pinfunction "P$1_P$2") (pintype "passive"))
      (node (ref "ZD14") (pin "P$2") (pinfunction "P$1_P$2") (pintype "passive"))
      (node (ref "ZD16") (pin "P$2") (pinfunction "P$1_P$2") (pintype "passive"))
      (node (ref "ZD18") (pin "P$2") (pinfunction "P$1_P$2") (pintype "passive"))
      (node (ref "ZD2") (pin "P$2") (pinfunction "P$1_P$2") (pintype "passive"))
      (node (ref "ZD20") (pin "P$2") (pinfunction "P$1_P$2") (pintype "passive"))
      (node (ref "ZD22") (pin "P$2") (pinfunction "P$1_P$2") (pintype "passive"))
      (node (ref "ZD24") (pin "P$2") (pinfunction "P$1_P$2") (pintype "passive"))
      (node (ref "ZD26") (pin "P$2") (pinfunction "P$1_P$2") (pintype "passive"))
      (node (ref "ZD28") (pin "P$2") (pinfunction "P$1_P$2") (pintype "passive"))
      (node (ref "ZD30") (pin "P$2") (pinfunction "P$1_P$2") (pintype "passive"))
      (node (ref "ZD32") (pin "P$2") (pinfunction "P$1_P$2") (pintype "passive"))
      (node (ref "ZD4") (pin "P$2") (pinfunction "P$1_P$2") (pintype "passive"))
      (node (ref "ZD6") (pin "P$2") (pinfunction "P$1_P$2") (pintype "passive"))
      (node (ref "ZD8") (pin "P$2") (pinfunction "P$1_P$2") (pintype "passive"))
    )
    (net (code "55") (name "CLR") (class "Default")
      (node (ref "IC1") (pin "10") (pinfunction "SCL_10") (pintype "input"))
      (node (ref "IC2") (pin "10") (pinfunction "SCL_10") (pintype "input"))
      (node (ref "IC3") (pin "10") (pinfunction "SCL_10") (pintype "input"))
      (node (ref "IC4") (pin "10") (pinfunction "SCL_10") (pintype "input"))
      (node (ref "JP1") (pin "7") (pinfunction "7_7") (pintype "passive"))
      (node (ref "JP2") (pin "7") (pinfunction "7_7") (pintype "passive"))
    )
    (net (code "56") (name "FETOE") (class "Default")
      (node (ref "DRV$1") (pin "12") (pinfunction "OE_12") (pintype "bidirectional"))
      (node (ref "DRV$10") (pin "12") (pinfunction "OE_12") (pintype "bidirectional"))
      (node (ref "DRV$11") (pin "12") (pinfunction "OE_12") (pintype "bidirectional"))
      (node (ref "DRV$12") (pin "12") (pinfunction "OE_12") (pintype "bidirectional"))
      (node (ref "DRV$13") (pin "12") (pinfunction "OE_12") (pintype "bidirectional"))
      (node (ref "DRV$14") (pin "12") (pinfunction "OE_12") (pintype "bidirectional"))
      (node (ref "DRV$15") (pin "12") (pinfunction "OE_12") (pintype "bidirectional"))
      (node (ref "DRV$16") (pin "12") (pinfunction "OE_12") (pintype "bidirectional"))
      (node (ref "DRV$2") (pin "12") (pinfunction "OE_12") (pintype "bidirectional"))
      (node (ref "DRV$3") (pin "12") (pinfunction "OE_12") (pintype "bidirectional"))
      (node (ref "DRV$4") (pin "12") (pinfunction "OE_12") (pintype "bidirectional"))
      (node (ref "DRV$5") (pin "12") (pinfunction "OE_12") (pintype "bidirectional"))
      (node (ref "DRV$6") (pin "12") (pinfunction "OE_12") (pintype "bidirectional"))
      (node (ref "DRV$7") (pin "12") (pinfunction "OE_12") (pintype "bidirectional"))
      (node (ref "DRV$8") (pin "12") (pinfunction "OE_12") (pintype "bidirectional"))
      (node (ref "DRV$9") (pin "12") (pinfunction "OE_12") (pintype "bidirectional"))
      (node (ref "JP1") (pin "8") (pinfunction "8_8") (pintype "passive"))
      (node (ref "JP2") (pin "8") (pinfunction "8_8") (pintype "passive"))
    )
    (net (code "57") (name "GND") (class "Default")
      (node (ref "C12") (pin "2") (pinfunction "2_2") (pintype "passive"))
      (node (ref "C16") (pin "2") (pinfunction "2_2") (pintype "passive"))
      (node (ref "C20") (pin "2") (pinfunction "2_2") (pintype "passive"))
      (node (ref "C24") (pin "2") (pinfunction "2_2") (pintype "passive"))
      (node (ref "C28") (pin "2") (pinfunction "2_2") (pintype "passive"))
      (node (ref "C32") (pin "2") (pinfunction "2_2") (pintype "passive"))
      (node (ref "C36") (pin "2") (pinfunction "2_2") (pintype "passive"))
      (node (ref "C4") (pin "2") (pinfunction "2_2") (pintype "passive"))
      (node (ref "C40") (pin "2") (pinfunction "2_2") (pintype "passive"))
      (node (ref "C44") (pin "2") (pinfunction "2_2") (pintype "passive"))
      (node (ref "C48") (pin "2") (pinfunction "2_2") (pintype "passive"))
      (node (ref "C52") (pin "2") (pinfunction "2_2") (pintype "passive"))
      (node (ref "C56") (pin "2") (pinfunction "2_2") (pintype "passive"))
      (node (ref "C60") (pin "2") (pinfunction "2_2") (pintype "passive"))
      (node (ref "C64") (pin "2") (pinfunction "2_2") (pintype "passive"))
      (node (ref "C8") (pin "2") (pinfunction "2_2") (pintype "passive"))
      (node (ref "DRV$1") (pin "2") (pinfunction "VL_2") (pintype "bidirectional"))
      (node (ref "DRV$1") (pin "4") (pinfunction "GND_4") (pintype "bidirectional"))
      (node (ref "DRV$1") (pin "5") (pinfunction "VSS1_5") (pintype "bidirectional"))
      (node (ref "DRV$1") (pin "6") (pinfunction "VSS2_6") (pintype "bidirectional"))
      (node (ref "DRV$1") (pin "THP") (pinfunction "VSS1_THP") (pintype "bidirectional"))
      (node (ref "DRV$1") (pin "THV$1") (pinfunction "VSS1_THV$1") (pintype "bidirectional"))
      (node (ref "DRV$1") (pin "THV$2") (pinfunction "VSS1_THV$2") (pintype "bidirectional"))
      (node (ref "DRV$1") (pin "THV$3") (pinfunction "VSS1_THV$3") (pintype "bidirectional"))
      (node (ref "DRV$1") (pin "THV$4") (pinfunction "VSS1_THV$4") (pintype "bidirectional"))
      (node (ref "DRV$10") (pin "2") (pinfunction "VL_2") (pintype "bidirectional"))
      (node (ref "DRV$10") (pin "4") (pinfunction "GND_4") (pintype "bidirectional"))
      (node (ref "DRV$10") (pin "5") (pinfunction "VSS1_5") (pintype "bidirectional"))
      (node (ref "DRV$10") (pin "6") (pinfunction "VSS2_6") (pintype "bidirectional"))
      (node (ref "DRV$10") (pin "THP") (pinfunction "VSS1_THP") (pintype "bidirectional"))
      (node (ref "DRV$10") (pin "THV$1") (pinfunction "VSS1_THV$1") (pintype "bidirectional"))
      (node (ref "DRV$10") (pin "THV$2") (pinfunction "VSS1_THV$2") (pintype "bidirectional"))
      (node (ref "DRV$10") (pin "THV$3") (pinfunction "VSS1_THV$3") (pintype "bidirectional"))
      (node (ref "DRV$10") (pin "THV$4") (pinfunction "VSS1_THV$4") (pintype "bidirectional"))
      (node (ref "DRV$11") (pin "2") (pinfunction "VL_2") (pintype "bidirectional"))
      (node (ref "DRV$11") (pin "4") (pinfunction "GND_4") (pintype "bidirectional"))
      (node (ref "DRV$11") (pin "5") (pinfunction "VSS1_5") (pintype "bidirectional"))
      (node (ref "DRV$11") (pin "6") (pinfunction "VSS2_6") (pintype "bidirectional"))
      (node (ref "DRV$11") (pin "THP") (pinfunction "VSS1_THP") (pintype "bidirectional"))
      (node (ref "DRV$11") (pin "THV$1") (pinfunction "VSS1_THV$1") (pintype "bidirectional"))
      (node (ref "DRV$11") (pin "THV$2") (pinfunction "VSS1_THV$2") (pintype "bidirectional"))
      (node (ref "DRV$11") (pin "THV$3") (pinfunction "VSS1_THV$3") (pintype "bidirectional"))
      (node (ref "DRV$11") (pin "THV$4") (pinfunction "VSS1_THV$4") (pintype "bidirectional"))
      (node (ref "DRV$12") (pin "2") (pinfunction "VL_2") (pintype "bidirectional"))
      (node (ref "DRV$12") (pin "4") (pinfunction "GND_4") (pintype "bidirectional"))
      (node (ref "DRV$12") (pin "5") (pinfunction "VSS1_5") (pintype "bidirectional"))
      (node (ref "DRV$12") (pin "6") (pinfunction "VSS2_6") (pintype "bidirectional"))
      (node (ref "DRV$12") (pin "THP") (pinfunction "VSS1_THP") (pintype "bidirectional"))
      (node (ref "DRV$12") (pin "THV$1") (pinfunction "VSS1_THV$1") (pintype "bidirectional"))
      (node (ref "DRV$12") (pin "THV$2") (pinfunction "VSS1_THV$2") (pintype "bidirectional"))
      (node (ref "DRV$12") (pin "THV$3") (pinfunction "VSS1_THV$3") (pintype "bidirectional"))
      (node (ref "DRV$12") (pin "THV$4") (pinfunction "VSS1_THV$4") (pintype "bidirectional"))
      (node (ref "DRV$13") (pin "2") (pinfunction "VL_2") (pintype "bidirectional"))
      (node (ref "DRV$13") (pin "4") (pinfunction "GND_4") (pintype "bidirectional"))
      (node (ref "DRV$13") (pin "5") (pinfunction "VSS1_5") (pintype "bidirectional"))
      (node (ref "DRV$13") (pin "6") (pinfunction "VSS2_6") (pintype "bidirectional"))
      (node (ref "DRV$13") (pin "THP") (pinfunction "VSS1_THP") (pintype "bidirectional"))
      (node (ref "DRV$13") (pin "THV$1") (pinfunction "VSS1_THV$1") (pintype "bidirectional"))
      (node (ref "DRV$13") (pin "THV$2") (pinfunction "VSS1_THV$2") (pintype "bidirectional"))
      (node (ref "DRV$13") (pin "THV$3") (pinfunction "VSS1_THV$3") (pintype "bidirectional"))
      (node (ref "DRV$13") (pin "THV$4") (pinfunction "VSS1_THV$4") (pintype "bidirectional"))
      (node (ref "DRV$14") (pin "2") (pinfunction "VL_2") (pintype "bidirectional"))
      (node (ref "DRV$14") (pin "4") (pinfunction "GND_4") (pintype "bidirectional"))
      (node (ref "DRV$14") (pin "5") (pinfunction "VSS1_5") (pintype "bidirectional"))
      (node (ref "DRV$14") (pin "6") (pinfunction "VSS2_6") (pintype "bidirectional"))
      (node (ref "DRV$14") (pin "THP") (pinfunction "VSS1_THP") (pintype "bidirectional"))
      (node (ref "DRV$14") (pin "THV$1") (pinfunction "VSS1_THV$1") (pintype "bidirectional"))
      (node (ref "DRV$14") (pin "THV$2") (pinfunction "VSS1_THV$2") (pintype "bidirectional"))
      (node (ref "DRV$14") (pin "THV$3") (pinfunction "VSS1_THV$3") (pintype "bidirectional"))
      (node (ref "DRV$14") (pin "THV$4") (pinfunction "VSS1_THV$4") (pintype "bidirectional"))
      (node (ref "DRV$15") (pin "2") (pinfunction "VL_2") (pintype "bidirectional"))
      (node (ref "DRV$15") (pin "4") (pinfunction "GND_4") (pintype "bidirectional"))
      (node (ref "DRV$15") (pin "5") (pinfunction "VSS1_5") (pintype "bidirectional"))
      (node (ref "DRV$15") (pin "6") (pinfunction "VSS2_6") (pintype "bidirectional"))
      (node (ref "DRV$15") (pin "THP") (pinfunction "VSS1_THP") (pintype "bidirectional"))
      (node (ref "DRV$15") (pin "THV$1") (pinfunction "VSS1_THV$1") (pintype "bidirectional"))
      (node (ref "DRV$15") (pin "THV$2") (pinfunction "VSS1_THV$2") (pintype "bidirectional"))
      (node (ref "DRV$15") (pin "THV$3") (pinfunction "VSS1_THV$3") (pintype "bidirectional"))
      (node (ref "DRV$15") (pin "THV$4") (pinfunction "VSS1_THV$4") (pintype "bidirectional"))
      (node (ref "DRV$16") (pin "2") (pinfunction "VL_2") (pintype "bidirectional"))
      (node (ref "DRV$16") (pin "4") (pinfunction "GND_4") (pintype "bidirectional"))
      (node (ref "DRV$16") (pin "5") (pinfunction "VSS1_5") (pintype "bidirectional"))
      (node (ref "DRV$16") (pin "6") (pinfunction "VSS2_6") (pintype "bidirectional"))
      (node (ref "DRV$16") (pin "THP") (pinfunction "VSS1_THP") (pintype "bidirectional"))
      (node (ref "DRV$16") (pin "THV$1") (pinfunction "VSS1_THV$1") (pintype "bidirectional"))
      (node (ref "DRV$16") (pin "THV$2") (pinfunction "VSS1_THV$2") (pintype "bidirectional"))
      (node (ref "DRV$16") (pin "THV$3") (pinfunction "VSS1_THV$3") (pintype "bidirectional"))
      (node (ref "DRV$16") (pin "THV$4") (pinfunction "VSS1_THV$4") (pintype "bidirectional"))
      (node (ref "DRV$2") (pin "2") (pinfunction "VL_2") (pintype "bidirectional"))
      (node (ref "DRV$2") (pin "4") (pinfunction "GND_4") (pintype "bidirectional"))
      (node (ref "DRV$2") (pin "5") (pinfunction "VSS1_5") (pintype "bidirectional"))
      (node (ref "DRV$2") (pin "6") (pinfunction "VSS2_6") (pintype "bidirectional"))
      (node (ref "DRV$2") (pin "THP") (pinfunction "VSS1_THP") (pintype "bidirectional"))
      (node (ref "DRV$2") (pin "THV$1") (pinfunction "VSS1_THV$1") (pintype "bidirectional"))
      (node (ref "DRV$2") (pin "THV$2") (pinfunction "VSS1_THV$2") (pintype "bidirectional"))
      (node (ref "DRV$2") (pin "THV$3") (pinfunction "VSS1_THV$3") (pintype "bidirectional"))
      (node (ref "DRV$2") (pin "THV$4") (pinfunction "VSS1_THV$4") (pintype "bidirectional"))
      (node (ref "DRV$3") (pin "2") (pinfunction "VL_2") (pintype "bidirectional"))
      (node (ref "DRV$3") (pin "4") (pinfunction "GND_4") (pintype "bidirectional"))
      (node (ref "DRV$3") (pin "5") (pinfunction "VSS1_5") (pintype "bidirectional"))
      (node (ref "DRV$3") (pin "6") (pinfunction "VSS2_6") (pintype "bidirectional"))
      (node (ref "DRV$3") (pin "THP") (pinfunction "VSS1_THP") (pintype "bidirectional"))
      (node (ref "DRV$3") (pin "THV$1") (pinfunction "VSS1_THV$1") (pintype "bidirectional"))
      (node (ref "DRV$3") (pin "THV$2") (pinfunction "VSS1_THV$2") (pintype "bidirectional"))
      (node (ref "DRV$3") (pin "THV$3") (pinfunction "VSS1_THV$3") (pintype "bidirectional"))
      (node (ref "DRV$3") (pin "THV$4") (pinfunction "VSS1_THV$4") (pintype "bidirectional"))
      (node (ref "DRV$4") (pin "2") (pinfunction "VL_2") (pintype "bidirectional"))
      (node (ref "DRV$4") (pin "4") (pinfunction "GND_4") (pintype "bidirectional"))
      (node (ref "DRV$4") (pin "5") (pinfunction "VSS1_5") (pintype "bidirectional"))
      (node (ref "DRV$4") (pin "6") (pinfunction "VSS2_6") (pintype "bidirectional"))
      (node (ref "DRV$4") (pin "THP") (pinfunction "VSS1_THP") (pintype "bidirectional"))
      (node (ref "DRV$4") (pin "THV$1") (pinfunction "VSS1_THV$1") (pintype "bidirectional"))
      (node (ref "DRV$4") (pin "THV$2") (pinfunction "VSS1_THV$2") (pintype "bidirectional"))
      (node (ref "DRV$4") (pin "THV$3") (pinfunction "VSS1_THV$3") (pintype "bidirectional"))
      (node (ref "DRV$4") (pin "THV$4") (pinfunction "VSS1_THV$4") (pintype "bidirectional"))
      (node (ref "DRV$5") (pin "2") (pinfunction "VL_2") (pintype "bidirectional"))
      (node (ref "DRV$5") (pin "4") (pinfunction "GND_4") (pintype "bidirectional"))
      (node (ref "DRV$5") (pin "5") (pinfunction "VSS1_5") (pintype "bidirectional"))
      (node (ref "DRV$5") (pin "6") (pinfunction "VSS2_6") (pintype "bidirectional"))
      (node (ref "DRV$5") (pin "THP") (pinfunction "VSS1_THP") (pintype "bidirectional"))
      (node (ref "DRV$5") (pin "THV$1") (pinfunction "VSS1_THV$1") (pintype "bidirectional"))
      (node (ref "DRV$5") (pin "THV$2") (pinfunction "VSS1_THV$2") (pintype "bidirectional"))
      (node (ref "DRV$5") (pin "THV$3") (pinfunction "VSS1_THV$3") (pintype "bidirectional"))
      (node (ref "DRV$5") (pin "THV$4") (pinfunction "VSS1_THV$4") (pintype "bidirectional"))
      (node (ref "DRV$6") (pin "2") (pinfunction "VL_2") (pintype "bidirectional"))
      (node (ref "DRV$6") (pin "4") (pinfunction "GND_4") (pintype "bidirectional"))
      (node (ref "DRV$6") (pin "5") (pinfunction "VSS1_5") (pintype "bidirectional"))
      (node (ref "DRV$6") (pin "6") (pinfunction "VSS2_6") (pintype "bidirectional"))
      (node (ref "DRV$6") (pin "THP") (pinfunction "VSS1_THP") (pintype "bidirectional"))
      (node (ref "DRV$6") (pin "THV$1") (pinfunction "VSS1_THV$1") (pintype "bidirectional"))
      (node (ref "DRV$6") (pin "THV$2") (pinfunction "VSS1_THV$2") (pintype "bidirectional"))
      (node (ref "DRV$6") (pin "THV$3") (pinfunction "VSS1_THV$3") (pintype "bidirectional"))
      (node (ref "DRV$6") (pin "THV$4") (pinfunction "VSS1_THV$4") (pintype "bidirectional"))
      (node (ref "DRV$7") (pin "2") (pinfunction "VL_2") (pintype "bidirectional"))
      (node (ref "DRV$7") (pin "4") (pinfunction "GND_4") (pintype "bidirectional"))
      (node (ref "DRV$7") (pin "5") (pinfunction "VSS1_5") (pintype "bidirectional"))
      (node (ref "DRV$7") (pin "6") (pinfunction "VSS2_6") (pintype "bidirectional"))
      (node (ref "DRV$7") (pin "THP") (pinfunction "VSS1_THP") (pintype "bidirectional"))
      (node (ref "DRV$7") (pin "THV$1") (pinfunction "VSS1_THV$1") (pintype "bidirectional"))
      (node (ref "DRV$7") (pin "THV$2") (pinfunction "VSS1_THV$2") (pintype "bidirectional"))
      (node (ref "DRV$7") (pin "THV$3") (pinfunction "VSS1_THV$3") (pintype "bidirectional"))
      (node (ref "DRV$7") (pin "THV$4") (pinfunction "VSS1_THV$4") (pintype "bidirectional"))
      (node (ref "DRV$8") (pin "2") (pinfunction "VL_2") (pintype "bidirectional"))
      (node (ref "DRV$8") (pin "4") (pinfunction "GND_4") (pintype "bidirectional"))
      (node (ref "DRV$8") (pin "5") (pinfunction "VSS1_5") (pintype "bidirectional"))
      (node (ref "DRV$8") (pin "6") (pinfunction "VSS2_6") (pintype "bidirectional"))
      (node (ref "DRV$8") (pin "THP") (pinfunction "VSS1_THP") (pintype "bidirectional"))
      (node (ref "DRV$8") (pin "THV$1") (pinfunction "VSS1_THV$1") (pintype "bidirectional"))
      (node (ref "DRV$8") (pin "THV$2") (pinfunction "VSS1_THV$2") (pintype "bidirectional"))
      (node (ref "DRV$8") (pin "THV$3") (pinfunction "VSS1_THV$3") (pintype "bidirectional"))
      (node (ref "DRV$8") (pin "THV$4") (pinfunction "VSS1_THV$4") (pintype "bidirectional"))
      (node (ref "DRV$9") (pin "2") (pinfunction "VL_2") (pintype "bidirectional"))
      (node (ref "DRV$9") (pin "4") (pinfunction "GND_4") (pintype "bidirectional"))
      (node (ref "DRV$9") (pin "5") (pinfunction "VSS1_5") (pintype "bidirectional"))
      (node (ref "DRV$9") (pin "6") (pinfunction "VSS2_6") (pintype "bidirectional"))
      (node (ref "DRV$9") (pin "THP") (pinfunction "VSS1_THP") (pintype "bidirectional"))
      (node (ref "DRV$9") (pin "THV$1") (pinfunction "VSS1_THV$1") (pintype "bidirectional"))
      (node (ref "DRV$9") (pin "THV$2") (pinfunction "VSS1_THV$2") (pintype "bidirectional"))
      (node (ref "DRV$9") (pin "THV$3") (pinfunction "VSS1_THV$3") (pintype "bidirectional"))
      (node (ref "DRV$9") (pin "THV$4") (pinfunction "VSS1_THV$4") (pintype "bidirectional"))
      (node (ref "IC1") (pin "13") (pinfunction "G_13") (pintype "input"))
      (node (ref "IC1") (pin "8") (pinfunction "GND_8") (pintype "power_in"))
      (node (ref "IC2") (pin "13") (pinfunction "G_13") (pintype "input"))
      (node (ref "IC2") (pin "8") (pinfunction "GND_8") (pintype "power_in"))
      (node (ref "IC3") (pin "13") (pinfunction "G_13") (pintype "input"))
      (node (ref "IC3") (pin "8") (pinfunction "GND_8") (pintype "power_in"))
      (node (ref "IC4") (pin "13") (pinfunction "G_13") (pintype "input"))
      (node (ref "IC4") (pin "8") (pinfunction "GND_8") (pintype "power_in"))
      (node (ref "JP1") (pin "6") (pinfunction "6_6") (pintype "passive"))
      (node (ref "JP2") (pin "6") (pinfunction "6_6") (pintype "passive"))
      (node (ref "SJ1") (pin "1") (pinfunction "1_1") (pintype "passive"))
    )
    (net (code "58") (name "Net-(CMOS$1-GN)") (class "Default")
      (node (ref "C2") (pin "2") (pinfunction "2_2") (pintype "passive"))
      (node (ref "CMOS$1") (pin "2") (pinfunction "GN_2") (pintype "bidirectional"))
      (node (ref "R2") (pin "2") (pinfunction "2_2") (pintype "passive"))
      (node (ref "ZD2") (pin "P$1") (pinfunction "K_P$1") (pintype "passive"))
    )
    (net (code "59") (name "Net-(CMOS$1-GP)") (class "Default")
      (node (ref "C1") (pin "2") (pinfunction "2_2") (pintype "passive"))
      (node (ref "CMOS$1") (pin "4") (pinfunction "GP_4") (pintype "bidirectional"))
      (node (ref "R1") (pin "1") (pinfunction "1_1") (pintype "passive"))
      (node (ref "ZD1") (pin "P$2") (pinfunction "P$1_P$2") (pintype "passive"))
    )
    (net (code "60") (name "Net-(CMOS$2-GN)") (class "Default")
      (node (ref "C6") (pin "2") (pinfunction "2_2") (pintype "passive"))
      (node (ref "CMOS$2") (pin "2") (pinfunction "GN_2") (pintype "bidirectional"))
      (node (ref "R4") (pin "2") (pinfunction "2_2") (pintype "passive"))
      (node (ref "ZD4") (pin "P$1") (pinfunction "K_P$1") (pintype "passive"))
    )
    (net (code "61") (name "Net-(CMOS$2-GP)") (class "Default")
      (node (ref "C5") (pin "2") (pinfunction "2_2") (pintype "passive"))
      (node (ref "CMOS$2") (pin "4") (pinfunction "GP_4") (pintype "bidirectional"))
      (node (ref "R3") (pin "1") (pinfunction "1_1") (pintype "passive"))
      (node (ref "ZD3") (pin "P$2") (pinfunction "P$1_P$2") (pintype "passive"))
    )
    (net (code "62") (name "Net-(CMOS$3-GN)") (class "Default")
      (node (ref "C10") (pin "2") (pinfunction "2_2") (pintype "passive"))
      (node (ref "CMOS$3") (pin "2") (pinfunction "GN_2") (pintype "bidirectional"))
      (node (ref "R6") (pin "2") (pinfunction "2_2") (pintype "passive"))
      (node (ref "ZD6") (pin "P$1") (pinfunction "K_P$1") (pintype "passive"))
    )
    (net (code "63") (name "Net-(CMOS$3-GP)") (class "Default")
      (node (ref "C9") (pin "2") (pinfunction "2_2") (pintype "passive"))
      (node (ref "CMOS$3") (pin "4") (pinfunction "GP_4") (pintype "bidirectional"))
      (node (ref "R5") (pin "1") (pinfunction "1_1") (pintype "passive"))
      (node (ref "ZD5") (pin "P$2") (pinfunction "P$1_P$2") (pintype "passive"))
    )
    (net (code "64") (name "Net-(CMOS$4-GN)") (class "Default")
      (node (ref "C14") (pin "2") (pinfunction "2_2") (pintype "passive"))
      (node (ref "CMOS$4") (pin "2") (pinfunction "GN_2") (pintype "bidirectional"))
      (node (ref "R8") (pin "2") (pinfunction "2_2") (pintype "passive"))
      (node (ref "ZD8") (pin "P$1") (pinfunction "K_P$1") (pintype "passive"))
    )
    (net (code "65") (name "Net-(CMOS$4-GP)") (class "Default")
      (node (ref "C13") (pin "2") (pinfunction "2_2") (pintype "passive"))
      (node (ref "CMOS$4") (pin "4") (pinfunction "GP_4") (pintype "bidirectional"))
      (node (ref "R7") (pin "1") (pinfunction "1_1") (pintype "passive"))
      (node (ref "ZD7") (pin "P$2") (pinfunction "P$1_P$2") (pintype "passive"))
    )
    (net (code "66") (name "Net-(CMOS$5-GN)") (class "Default")
      (node (ref "C18") (pin "2") (pinfunction "2_2") (pintype "passive"))
      (node (ref "CMOS$5") (pin "2") (pinfunction "GN_2") (pintype "bidirectional"))
      (node (ref "R10") (pin "2") (pinfunction "2_2") (pintype "passive"))
      (node (ref "ZD10") (pin "P$1") (pinfunction "K_P$1") (pintype "passive"))
    )
    (net (code "67") (name "Net-(CMOS$5-GP)") (class "Default")
      (node (ref "C17") (pin "2") (pinfunction "2_2") (pintype "passive"))
      (node (ref "CMOS$5") (pin "4") (pinfunction "GP_4") (pintype "bidirectional"))
      (node (ref "R9") (pin "1") (pinfunction "1_1") (pintype "passive"))
      (node (ref "ZD9") (pin "P$2") (pinfunction "P$1_P$2") (pintype "passive"))
    )
    (net (code "68") (name "Net-(CMOS$6-GN)") (class "Default")
      (node (ref "C22") (pin "2") (pinfunction "2_2") (pintype "passive"))
      (node (ref "CMOS$6") (pin "2") (pinfunction "GN_2") (pintype "bidirectional"))
      (node (ref "R12") (pin "2") (pinfunction "2_2") (pintype "passive"))
      (node (ref "ZD12") (pin "P$1") (pinfunction "K_P$1") (pintype "passive"))
    )
    (net (code "69") (name "Net-(CMOS$6-GP)") (class "Default")
      (node (ref "C21") (pin "2") (pinfunction "2_2") (pintype "passive"))
      (node (ref "CMOS$6") (pin "4") (pinfunction "GP_4") (pintype "bidirectional"))
      (node (ref "R11") (pin "1") (pinfunction "1_1") (pintype "passive"))
      (node (ref "ZD11") (pin "P$2") (pinfunction "P$1_P$2") (pintype "passive"))
    )
    (net (code "70") (name "Net-(CMOS$7-GN)") (class "Default")
      (node (ref "C26") (pin "2") (pinfunction "2_2") (pintype "passive"))
      (node (ref "CMOS$7") (pin "2") (pinfunction "GN_2") (pintype "bidirectional"))
      (node (ref "R14") (pin "2") (pinfunction "2_2") (pintype "passive"))
      (node (ref "ZD14") (pin "P$1") (pinfunction "K_P$1") (pintype "passive"))
    )
    (net (code "71") (name "Net-(CMOS$7-GP)") (class "Default")
      (node (ref "C25") (pin "2") (pinfunction "2_2") (pintype "passive"))
      (node (ref "CMOS$7") (pin "4") (pinfunction "GP_4") (pintype "bidirectional"))
      (node (ref "R13") (pin "1") (pinfunction "1_1") (pintype "passive"))
      (node (ref "ZD13") (pin "P$2") (pinfunction "P$1_P$2") (pintype "passive"))
    )
    (net (code "72") (name "Net-(CMOS$8-GN)") (class "Default")
      (node (ref "C30") (pin "2") (pinfunction "2_2") (pintype "passive"))
      (node (ref "CMOS$8") (pin "2") (pinfunction "GN_2") (pintype "bidirectional"))
      (node (ref "R16") (pin "2") (pinfunction "2_2") (pintype "passive"))
      (node (ref "ZD16") (pin "P$1") (pinfunction "K_P$1") (pintype "passive"))
    )
    (net (code "73") (name "Net-(CMOS$8-GP)") (class "Default")
      (node (ref "C29") (pin "2") (pinfunction "2_2") (pintype "passive"))
      (node (ref "CMOS$8") (pin "4") (pinfunction "GP_4") (pintype "bidirectional"))
      (node (ref "R15") (pin "1") (pinfunction "1_1") (pintype "passive"))
      (node (ref "ZD15") (pin "P$2") (pinfunction "P$1_P$2") (pintype "passive"))
    )
    (net (code "74") (name "Net-(CMOS$9-GN)") (class "Default")
      (node (ref "C34") (pin "2") (pinfunction "2_2") (pintype "passive"))
      (node (ref "CMOS$9") (pin "2") (pinfunction "GN_2") (pintype "bidirectional"))
      (node (ref "R18") (pin "2") (pinfunction "2_2") (pintype "passive"))
      (node (ref "ZD18") (pin "P$1") (pinfunction "K_P$1") (pintype "passive"))
    )
    (net (code "75") (name "Net-(CMOS$9-GP)") (class "Default")
      (node (ref "C33") (pin "2") (pinfunction "2_2") (pintype "passive"))
      (node (ref "CMOS$9") (pin "4") (pinfunction "GP_4") (pintype "bidirectional"))
      (node (ref "R17") (pin "1") (pinfunction "1_1") (pintype "passive"))
      (node (ref "ZD17") (pin "P$2") (pinfunction "P$1_P$2") (pintype "passive"))
    )
    (net (code "76") (name "Net-(CMOS$10-GN)") (class "Default")
      (node (ref "C38") (pin "2") (pinfunction "2_2") (pintype "passive"))
      (node (ref "CMOS$10") (pin "2") (pinfunction "GN_2") (pintype "bidirectional"))
      (node (ref "R20") (pin "2") (pinfunction "2_2") (pintype "passive"))
      (node (ref "ZD20") (pin "P$1") (pinfunction "K_P$1") (pintype "passive"))
    )
    (net (code "77") (name "Net-(CMOS$10-GP)") (class "Default")
      (node (ref "C37") (pin "2") (pinfunction "2_2") (pintype "passive"))
      (node (ref "CMOS$10") (pin "4") (pinfunction "GP_4") (pintype "bidirectional"))
      (node (ref "R19") (pin "1") (pinfunction "1_1") (pintype "passive"))
      (node (ref "ZD19") (pin "P$2") (pinfunction "P$1_P$2") (pintype "passive"))
    )
    (net (code "78") (name "Net-(CMOS$11-GN)") (class "Default")
      (node (ref "C42") (pin "2") (pinfunction "2_2") (pintype "passive"))
      (node (ref "CMOS$11") (pin "2") (pinfunction "GN_2") (pintype "bidirectional"))
      (node (ref "R22") (pin "2") (pinfunction "2_2") (pintype "passive"))
      (node (ref "ZD22") (pin "P$1") (pinfunction "K_P$1") (pintype "passive"))
    )
    (net (code "79") (name "Net-(CMOS$11-GP)") (class "Default")
      (node (ref "C41") (pin "2") (pinfunction "2_2") (pintype "passive"))
      (node (ref "CMOS$11") (pin "4") (pinfunction "GP_4") (pintype "bidirectional"))
      (node (ref "R21") (pin "1") (pinfunction "1_1") (pintype "passive"))
      (node (ref "ZD21") (pin "P$2") (pinfunction "P$1_P$2") (pintype "passive"))
    )
    (net (code "80") (name "Net-(CMOS$12-GN)") (class "Default")
      (node (ref "C46") (pin "2") (pinfunction "2_2") (pintype "passive"))
      (node (ref "CMOS$12") (pin "2") (pinfunction "GN_2") (pintype "bidirectional"))
      (node (ref "R24") (pin "2") (pinfunction "2_2") (pintype "passive"))
      (node (ref "ZD24") (pin "P$1") (pinfunction "K_P$1") (pintype "passive"))
    )
    (net (code "81") (name "Net-(CMOS$12-GP)") (class "Default")
      (node (ref "C45") (pin "2") (pinfunction "2_2") (pintype "passive"))
      (node (ref "CMOS$12") (pin "4") (pinfunction "GP_4") (pintype "bidirectional"))
      (node (ref "R23") (pin "1") (pinfunction "1_1") (pintype "passive"))
      (node (ref "ZD23") (pin "P$2") (pinfunction "P$1_P$2") (pintype "passive"))
    )
    (net (code "82") (name "Net-(CMOS$13-GN)") (class "Default")
      (node (ref "C50") (pin "2") (pinfunction "2_2") (pintype "passive"))
      (node (ref "CMOS$13") (pin "2") (pinfunction "GN_2") (pintype "bidirectional"))
      (node (ref "R26") (pin "2") (pinfunction "2_2") (pintype "passive"))
      (node (ref "ZD26") (pin "P$1") (pinfunction "K_P$1") (pintype "passive"))
    )
    (net (code "83") (name "Net-(CMOS$13-GP)") (class "Default")
      (node (ref "C49") (pin "2") (pinfunction "2_2") (pintype "passive"))
      (node (ref "CMOS$13") (pin "4") (pinfunction "GP_4") (pintype "bidirectional"))
      (node (ref "R25") (pin "1") (pinfunction "1_1") (pintype "passive"))
      (node (ref "ZD25") (pin "P$2") (pinfunction "P$1_P$2") (pintype "passive"))
    )
    (net (code "84") (name "Net-(CMOS$14-GN)") (class "Default")
      (node (ref "C54") (pin "2") (pinfunction "2_2") (pintype "passive"))
      (node (ref "CMOS$14") (pin "2") (pinfunction "GN_2") (pintype "bidirectional"))
      (node (ref "R28") (pin "2") (pinfunction "2_2") (pintype "passive"))
      (node (ref "ZD28") (pin "P$1") (pinfunction "K_P$1") (pintype "passive"))
    )
    (net (code "85") (name "Net-(CMOS$14-GP)") (class "Default")
      (node (ref "C53") (pin "2") (pinfunction "2_2") (pintype "passive"))
      (node (ref "CMOS$14") (pin "4") (pinfunction "GP_4") (pintype "bidirectional"))
      (node (ref "R27") (pin "1") (pinfunction "1_1") (pintype "passive"))
      (node (ref "ZD27") (pin "P$2") (pinfunction "P$1_P$2") (pintype "passive"))
    )
    (net (code "86") (name "Net-(CMOS$15-GN)") (class "Default")
      (node (ref "C58") (pin "2") (pinfunction "2_2") (pintype "passive"))
      (node (ref "CMOS$15") (pin "2") (pinfunction "GN_2") (pintype "bidirectional"))
      (node (ref "R30") (pin "2") (pinfunction "2_2") (pintype "passive"))
      (node (ref "ZD30") (pin "P$1") (pinfunction "K_P$1") (pintype "passive"))
    )
    (net (code "87") (name "Net-(CMOS$15-GP)") (class "Default")
      (node (ref "C57") (pin "2") (pinfunction "2_2") (pintype "passive"))
      (node (ref "CMOS$15") (pin "4") (pinfunction "GP_4") (pintype "bidirectional"))
      (node (ref "R29") (pin "1") (pinfunction "1_1") (pintype "passive"))
      (node (ref "ZD29") (pin "P$2") (pinfunction "P$1_P$2") (pintype "passive"))
    )
    (net (code "88") (name "Net-(CMOS$16-GN)") (class "Default")
      (node (ref "C62") (pin "2") (pinfunction "2_2") (pintype "passive"))
      (node (ref "CMOS$16") (pin "2") (pinfunction "GN_2") (pintype "bidirectional"))
      (node (ref "R32") (pin "2") (pinfunction "2_2") (pintype "passive"))
      (node (ref "ZD32") (pin "P$1") (pinfunction "K_P$1") (pintype "passive"))
    )
    (net (code "89") (name "Net-(CMOS$16-GP)") (class "Default")
      (node (ref "C61") (pin "2") (pinfunction "2_2") (pintype "passive"))
      (node (ref "CMOS$16") (pin "4") (pinfunction "GP_4") (pintype "bidirectional"))
      (node (ref "R31") (pin "1") (pinfunction "1_1") (pintype "passive"))
      (node (ref "ZD31") (pin "P$2") (pinfunction "P$1_P$2") (pintype "passive"))
    )
    (net (code "90") (name "Net-(D1-P$1)") (class "Default")
      (node (ref "CMOS$1") (pin "5") (pinfunction "DP_5") (pintype "bidirectional"))
      (node (ref "CMOS$1") (pin "6") (pinfunction "DP_6") (pintype "bidirectional"))
      (node (ref "D1") (pin "1") (pinfunction "P$1_1") (pintype "passive"))
    )
    (net (code "91") (name "Net-(D1-P$2)") (class "Default")
      (node (ref "CMOS$1") (pin "7") (pinfunction "DN_7") (pintype "bidirectional"))
      (node (ref "CMOS$1") (pin "8") (pinfunction "DN_8") (pintype "bidirectional"))
      (node (ref "D1") (pin "2") (pinfunction "P$2_2") (pintype "passive"))
    )
    (net (code "92") (name "Net-(D2-P$1)") (class "Default")
      (node (ref "CMOS$2") (pin "5") (pinfunction "DP_5") (pintype "bidirectional"))
      (node (ref "CMOS$2") (pin "6") (pinfunction "DP_6") (pintype "bidirectional"))
      (node (ref "D2") (pin "1") (pinfunction "P$1_1") (pintype "passive"))
    )
    (net (code "93") (name "Net-(D2-P$2)") (class "Default")
      (node (ref "CMOS$2") (pin "7") (pinfunction "DN_7") (pintype "bidirectional"))
      (node (ref "CMOS$2") (pin "8") (pinfunction "DN_8") (pintype "bidirectional"))
      (node (ref "D2") (pin "2") (pinfunction "P$2_2") (pintype "passive"))
    )
    (net (code "94") (name "Net-(D3-P$1)") (class "Default")
      (node (ref "CMOS$3") (pin "5") (pinfunction "DP_5") (pintype "bidirectional"))
      (node (ref "CMOS$3") (pin "6") (pinfunction "DP_6") (pintype "bidirectional"))
      (node (ref "D3") (pin "1") (pinfunction "P$1_1") (pintype "passive"))
    )
    (net (code "95") (name "Net-(D3-P$2)") (class "Default")
      (node (ref "CMOS$3") (pin "7") (pinfunction "DN_7") (pintype "bidirectional"))
      (node (ref "CMOS$3") (pin "8") (pinfunction "DN_8") (pintype "bidirectional"))
      (node (ref "D3") (pin "2") (pinfunction "P$2_2") (pintype "passive"))
    )
    (net (code "96") (name "Net-(D4-P$1)") (class "Default")
      (node (ref "CMOS$4") (pin "5") (pinfunction "DP_5") (pintype "bidirectional"))
      (node (ref "CMOS$4") (pin "6") (pinfunction "DP_6") (pintype "bidirectional"))
      (node (ref "D4") (pin "1") (pinfunction "P$1_1") (pintype "passive"))
    )
    (net (code "97") (name "Net-(D4-P$2)") (class "Default")
      (node (ref "CMOS$4") (pin "7") (pinfunction "DN_7") (pintype "bidirectional"))
      (node (ref "CMOS$4") (pin "8") (pinfunction "DN_8") (pintype "bidirectional"))
      (node (ref "D4") (pin "2") (pinfunction "P$2_2") (pintype "passive"))
    )
    (net (code "98") (name "Net-(D5-P$1)") (class "Default")
      (node (ref "CMOS$5") (pin "5") (pinfunction "DP_5") (pintype "bidirectional"))
      (node (ref "CMOS$5") (pin "6") (pinfunction "DP_6") (pintype "bidirectional"))
      (node (ref "D5") (pin "1") (pinfunction "P$1_1") (pintype "passive"))
    )
    (net (code "99") (name "Net-(D5-P$2)") (class "Default")
      (node (ref "CMOS$5") (pin "7") (pinfunction "DN_7") (pintype "bidirectional"))
      (node (ref "CMOS$5") (pin "8") (pinfunction "DN_8") (pintype "bidirectional"))
      (node (ref "D5") (pin "2") (pinfunction "P$2_2") (pintype "passive"))
    )
    (net (code "100") (name "Net-(D6-P$1)") (class "Default")
      (node (ref "CMOS$6") (pin "5") (pinfunction "DP_5") (pintype "bidirectional"))
      (node (ref "CMOS$6") (pin "6") (pinfunction "DP_6") (pintype "bidirectional"))
      (node (ref "D6") (pin "1") (pinfunction "P$1_1") (pintype "passive"))
    )
    (net (code "101") (name "Net-(D6-P$2)") (class "Default")
      (node (ref "CMOS$6") (pin "7") (pinfunction "DN_7") (pintype "bidirectional"))
      (node (ref "CMOS$6") (pin "8") (pinfunction "DN_8") (pintype "bidirectional"))
      (node (ref "D6") (pin "2") (pinfunction "P$2_2") (pintype "passive"))
    )
    (net (code "102") (name "Net-(D7-P$1)") (class "Default")
      (node (ref "CMOS$7") (pin "5") (pinfunction "DP_5") (pintype "bidirectional"))
      (node (ref "CMOS$7") (pin "6") (pinfunction "DP_6") (pintype "bidirectional"))
      (node (ref "D7") (pin "1") (pinfunction "P$1_1") (pintype "passive"))
    )
    (net (code "103") (name "Net-(D7-P$2)") (class "Default")
      (node (ref "CMOS$7") (pin "7") (pinfunction "DN_7") (pintype "bidirectional"))
      (node (ref "CMOS$7") (pin "8") (pinfunction "DN_8") (pintype "bidirectional"))
      (node (ref "D7") (pin "2") (pinfunction "P$2_2") (pintype "passive"))
    )
    (net (code "104") (name "Net-(D8-P$1)") (class "Default")
      (node (ref "CMOS$8") (pin "5") (pinfunction "DP_5") (pintype "bidirectional"))
      (node (ref "CMOS$8") (pin "6") (pinfunction "DP_6") (pintype "bidirectional"))
      (node (ref "D8") (pin "1") (pinfunction "P$1_1") (pintype "passive"))
    )
    (net (code "105") (name "Net-(D8-P$2)") (class "Default")
      (node (ref "CMOS$8") (pin "7") (pinfunction "DN_7") (pintype "bidirectional"))
      (node (ref "CMOS$8") (pin "8") (pinfunction "DN_8") (pintype "bidirectional"))
      (node (ref "D8") (pin "2") (pinfunction "P$2_2") (pintype "passive"))
    )
    (net (code "106") (name "Net-(D9-P$1)") (class "Default")
      (node (ref "CMOS$9") (pin "5") (pinfunction "DP_5") (pintype "bidirectional"))
      (node (ref "CMOS$9") (pin "6") (pinfunction "DP_6") (pintype "bidirectional"))
      (node (ref "D9") (pin "1") (pinfunction "P$1_1") (pintype "passive"))
    )
    (net (code "107") (name "Net-(D9-P$2)") (class "Default")
      (node (ref "CMOS$9") (pin "7") (pinfunction "DN_7") (pintype "bidirectional"))
      (node (ref "CMOS$9") (pin "8") (pinfunction "DN_8") (pintype "bidirectional"))
      (node (ref "D9") (pin "2") (pinfunction "P$2_2") (pintype "passive"))
    )
    (net (code "108") (name "Net-(D10-P$1)") (class "Default")
      (node (ref "CMOS$10") (pin "5") (pinfunction "DP_5") (pintype "bidirectional"))
      (node (ref "CMOS$10") (pin "6") (pinfunction "DP_6") (pintype "bidirectional"))
      (node (ref "D10") (pin "1") (pinfunction "P$1_1") (pintype "passive"))
    )
    (net (code "109") (name "Net-(D10-P$2)") (class "Default")
      (node (ref "CMOS$10") (pin "7") (pinfunction "DN_7") (pintype "bidirectional"))
      (node (ref "CMOS$10") (pin "8") (pinfunction "DN_8") (pintype "bidirectional"))
      (node (ref "D10") (pin "2") (pinfunction "P$2_2") (pintype "passive"))
    )
    (net (code "110") (name "Net-(D11-P$1)") (class "Default")
      (node (ref "CMOS$11") (pin "5") (pinfunction "DP_5") (pintype "bidirectional"))
      (node (ref "CMOS$11") (pin "6") (pinfunction "DP_6") (pintype "bidirectional"))
      (node (ref "D11") (pin "1") (pinfunction "P$1_1") (pintype "passive"))
    )
    (net (code "111") (name "Net-(D11-P$2)") (class "Default")
      (node (ref "CMOS$11") (pin "7") (pinfunction "DN_7") (pintype "bidirectional"))
      (node (ref "CMOS$11") (pin "8") (pinfunction "DN_8") (pintype "bidirectional"))
      (node (ref "D11") (pin "2") (pinfunction "P$2_2") (pintype "passive"))
    )
    (net (code "112") (name "Net-(D12-P$1)") (class "Default")
      (node (ref "CMOS$12") (pin "5") (pinfunction "DP_5") (pintype "bidirectional"))
      (node (ref "CMOS$12") (pin "6") (pinfunction "DP_6") (pintype "bidirectional"))
      (node (ref "D12") (pin "1") (pinfunction "P$1_1") (pintype "passive"))
    )
    (net (code "113") (name "Net-(D12-P$2)") (class "Default")
      (node (ref "CMOS$12") (pin "7") (pinfunction "DN_7") (pintype "bidirectional"))
      (node (ref "CMOS$12") (pin "8") (pinfunction "DN_8") (pintype "bidirectional"))
      (node (ref "D12") (pin "2") (pinfunction "P$2_2") (pintype "passive"))
    )
    (net (code "114") (name "Net-(D13-P$1)") (class "Default")
      (node (ref "CMOS$13") (pin "5") (pinfunction "DP_5") (pintype "bidirectional"))
      (node (ref "CMOS$13") (pin "6") (pinfunction "DP_6") (pintype "bidirectional"))
      (node (ref "D13") (pin "1") (pinfunction "P$1_1") (pintype "passive"))
    )
    (net (code "115") (name "Net-(D13-P$2)") (class "Default")
      (node (ref "CMOS$13") (pin "7") (pinfunction "DN_7") (pintype "bidirectional"))
      (node (ref "CMOS$13") (pin "8") (pinfunction "DN_8") (pintype "bidirectional"))
      (node (ref "D13") (pin "2") (pinfunction "P$2_2") (pintype "passive"))
    )
    (net (code "116") (name "Net-(D14-P$1)") (class "Default")
      (node (ref "CMOS$14") (pin "5") (pinfunction "DP_5") (pintype "bidirectional"))
      (node (ref "CMOS$14") (pin "6") (pinfunction "DP_6") (pintype "bidirectional"))
      (node (ref "D14") (pin "1") (pinfunction "P$1_1") (pintype "passive"))
    )
    (net (code "117") (name "Net-(D14-P$2)") (class "Default")
      (node (ref "CMOS$14") (pin "7") (pinfunction "DN_7") (pintype "bidirectional"))
      (node (ref "CMOS$14") (pin "8") (pinfunction "DN_8") (pintype "bidirectional"))
      (node (ref "D14") (pin "2") (pinfunction "P$2_2") (pintype "passive"))
    )
    (net (code "118") (name "Net-(D15-P$1)") (class "Default")
      (node (ref "CMOS$15") (pin "5") (pinfunction "DP_5") (pintype "bidirectional"))
      (node (ref "CMOS$15") (pin "6") (pinfunction "DP_6") (pintype "bidirectional"))
      (node (ref "D15") (pin "1") (pinfunction "P$1_1") (pintype "passive"))
    )
    (net (code "119") (name "Net-(D15-P$2)") (class "Default")
      (node (ref "CMOS$15") (pin "7") (pinfunction "DN_7") (pintype "bidirectional"))
      (node (ref "CMOS$15") (pin "8") (pinfunction "DN_8") (pintype "bidirectional"))
      (node (ref "D15") (pin "2") (pinfunction "P$2_2") (pintype "passive"))
    )
    (net (code "120") (name "Net-(D16-P$1)") (class "Default")
      (node (ref "CMOS$16") (pin "5") (pinfunction "DP_5") (pintype "bidirectional"))
      (node (ref "CMOS$16") (pin "6") (pinfunction "DP_6") (pintype "bidirectional"))
      (node (ref "D16") (pin "1") (pinfunction "P$1_1") (pintype "passive"))
    )
    (net (code "121") (name "Net-(D16-P$2)") (class "Default")
      (node (ref "CMOS$16") (pin "7") (pinfunction "DN_7") (pintype "bidirectional"))
      (node (ref "CMOS$16") (pin "8") (pinfunction "DN_8") (pintype "bidirectional"))
      (node (ref "D16") (pin "2") (pinfunction "P$2_2") (pintype "passive"))
    )
    (net (code "122") (name "Net-(DRV$1-OUTA)") (class "Default")
      (node (ref "C1") (pin "1") (pinfunction "1_1") (pintype "passive"))
      (node (ref "DRV$1") (pin "9") (pinfunction "OUTA_9") (pintype "bidirectional"))
    )
    (net (code "123") (name "Net-(DRV$1-OUTB)") (class "Default")
      (node (ref "C2") (pin "1") (pinfunction "1_1") (pintype "passive"))
      (node (ref "DRV$1") (pin "7") (pinfunction "OUTB_7") (pintype "bidirectional"))
    )
    (net (code "124") (name "Net-(DRV$2-OUTA)") (class "Default")
      (node (ref "C5") (pin "1") (pinfunction "1_1") (pintype "passive"))
      (node (ref "DRV$2") (pin "9") (pinfunction "OUTA_9") (pintype "bidirectional"))
    )
    (net (code "125") (name "Net-(DRV$2-OUTB)") (class "Default")
      (node (ref "C6") (pin "1") (pinfunction "1_1") (pintype "passive"))
      (node (ref "DRV$2") (pin "7") (pinfunction "OUTB_7") (pintype "bidirectional"))
    )
    (net (code "126") (name "Net-(DRV$3-OUTA)") (class "Default")
      (node (ref "C9") (pin "1") (pinfunction "1_1") (pintype "passive"))
      (node (ref "DRV$3") (pin "9") (pinfunction "OUTA_9") (pintype "bidirectional"))
    )
    (net (code "127") (name "Net-(DRV$3-OUTB)") (class "Default")
      (node (ref "C10") (pin "1") (pinfunction "1_1") (pintype "passive"))
      (node (ref "DRV$3") (pin "7") (pinfunction "OUTB_7") (pintype "bidirectional"))
    )
    (net (code "128") (name "Net-(DRV$4-OUTA)") (class "Default")
      (node (ref "C13") (pin "1") (pinfunction "1_1") (pintype "passive"))
      (node (ref "DRV$4") (pin "9") (pinfunction "OUTA_9") (pintype "bidirectional"))
    )
    (net (code "129") (name "Net-(DRV$4-OUTB)") (class "Default")
      (node (ref "C14") (pin "1") (pinfunction "1_1") (pintype "passive"))
      (node (ref "DRV$4") (pin "7") (pinfunction "OUTB_7") (pintype "bidirectional"))
    )
    (net (code "130") (name "Net-(DRV$5-OUTA)") (class "Default")
      (node (ref "C17") (pin "1") (pinfunction "1_1") (pintype "passive"))
      (node (ref "DRV$5") (pin "9") (pinfunction "OUTA_9") (pintype "bidirectional"))
    )
    (net (code "131") (name "Net-(DRV$5-OUTB)") (class "Default")
      (node (ref "C18") (pin "1") (pinfunction "1_1") (pintype "passive"))
      (node (ref "DRV$5") (pin "7") (pinfunction "OUTB_7") (pintype "bidirectional"))
    )
    (net (code "132") (name "Net-(DRV$6-OUTA)") (class "Default")
      (node (ref "C21") (pin "1") (pinfunction "1_1") (pintype "passive"))
      (node (ref "DRV$6") (pin "9") (pinfunction "OUTA_9") (pintype "bidirectional"))
    )
    (net (code "133") (name "Net-(DRV$6-OUTB)") (class "Default")
      (node (ref "C22") (pin "1") (pinfunction "1_1") (pintype "passive"))
      (node (ref "DRV$6") (pin "7") (pinfunction "OUTB_7") (pintype "bidirectional"))
    )
    (net (code "134") (name "Net-(DRV$7-OUTA)") (class "Default")
      (node (ref "C25") (pin "1") (pinfunction "1_1") (pintype "passive"))
      (node (ref "DRV$7") (pin "9") (pinfunction "OUTA_9") (pintype "bidirectional"))
    )
    (net (code "135") (name "Net-(DRV$7-OUTB)") (class "Default")
      (node (ref "C26") (pin "1") (pinfunction "1_1") (pintype "passive"))
      (node (ref "DRV$7") (pin "7") (pinfunction "OUTB_7") (pintype "bidirectional"))
    )
    (net (code "136") (name "Net-(DRV$8-OUTA)") (class "Default")
      (node (ref "C29") (pin "1") (pinfunction "1_1") (pintype "passive"))
      (node (ref "DRV$8") (pin "9") (pinfunction "OUTA_9") (pintype "bidirectional"))
    )
    (net (code "137") (name "Net-(DRV$8-OUTB)") (class "Default")
      (node (ref "C30") (pin "1") (pinfunction "1_1") (pintype "passive"))
      (node (ref "DRV$8") (pin "7") (pinfunction "OUTB_7") (pintype "bidirectional"))
    )
    (net (code "138") (name "Net-(DRV$9-OUTA)") (class "Default")
      (node (ref "C33") (pin "1") (pinfunction "1_1") (pintype "passive"))
      (node (ref "DRV$9") (pin "9") (pinfunction "OUTA_9") (pintype "bidirectional"))
    )
    (net (code "139") (name "Net-(DRV$9-OUTB)") (class "Default")
      (node (ref "C34") (pin "1") (pinfunction "1_1") (pintype "passive"))
      (node (ref "DRV$9") (pin "7") (pinfunction "OUTB_7") (pintype "bidirectional"))
    )
    (net (code "140") (name "Net-(DRV$10-OUTA)") (class "Default")
      (node (ref "C37") (pin "1") (pinfunction "1_1") (pintype "passive"))
      (node (ref "DRV$10") (pin "9") (pinfunction "OUTA_9") (pintype "bidirectional"))
    )
    (net (code "141") (name "Net-(DRV$10-OUTB)") (class "Default")
      (node (ref "C38") (pin "1") (pinfunction "1_1") (pintype "passive"))
      (node (ref "DRV$10") (pin "7") (pinfunction "OUTB_7") (pintype "bidirectional"))
    )
    (net (code "142") (name "Net-(DRV$11-OUTA)") (class "Default")
      (node (ref "C41") (pin "1") (pinfunction "1_1") (pintype "passive"))
      (node (ref "DRV$11") (pin "9") (pinfunction "OUTA_9") (pintype "bidirectional"))
    )
    (net (code "143") (name "Net-(DRV$11-OUTB)") (class "Default")
      (node (ref "C42") (pin "1") (pinfunction "1_1") (pintype "passive"))
      (node (ref "DRV$11") (pin "7") (pinfunction "OUTB_7") (pintype "bidirectional"))
    )
    (net (code "144") (name "Net-(DRV$12-OUTA)") (class "Default")
      (node (ref "C45") (pin "1") (pinfunction "1_1") (pintype "passive"))
      (node (ref "DRV$12") (pin "9") (pinfunction "OUTA_9") (pintype "bidirectional"))
    )
    (net (code "145") (name "Net-(DRV$12-OUTB)") (class "Default")
      (node (ref "C46") (pin "1") (pinfunction "1_1") (pintype "passive"))
      (node (ref "DRV$12") (pin "7") (pinfunction "OUTB_7") (pintype "bidirectional"))
    )
    (net (code "146") (name "Net-(DRV$13-OUTA)") (class "Default")
      (node (ref "C49") (pin "1") (pinfunction "1_1") (pintype "passive"))
      (node (ref "DRV$13") (pin "9") (pinfunction "OUTA_9") (pintype "bidirectional"))
    )
    (net (code "147") (name "Net-(DRV$13-OUTB)") (class "Default")
      (node (ref "C50") (pin "1") (pinfunction "1_1") (pintype "passive"))
      (node (ref "DRV$13") (pin "7") (pinfunction "OUTB_7") (pintype "bidirectional"))
    )
    (net (code "148") (name "Net-(DRV$14-OUTA)") (class "Default")
      (node (ref "C53") (pin "1") (pinfunction "1_1") (pintype "passive"))
      (node (ref "DRV$14") (pin "9") (pinfunction "OUTA_9") (pintype "bidirectional"))
    )
    (net (code "149") (name "Net-(DRV$14-OUTB)") (class "Default")
      (node (ref "C54") (pin "1") (pinfunction "1_1") (pintype "passive"))
      (node (ref "DRV$14") (pin "7") (pinfunction "OUTB_7") (pintype "bidirectional"))
    )
    (net (code "150") (name "Net-(DRV$15-OUTA)") (class "Default")
      (node (ref "C57") (pin "1") (pinfunction "1_1") (pintype "passive"))
      (node (ref "DRV$15") (pin "9") (pinfunction "OUTA_9") (pintype "bidirectional"))
    )
    (net (code "151") (name "Net-(DRV$15-OUTB)") (class "Default")
      (node (ref "C58") (pin "1") (pinfunction "1_1") (pintype "passive"))
      (node (ref "DRV$15") (pin "7") (pinfunction "OUTB_7") (pintype "bidirectional"))
    )
    (net (code "152") (name "Net-(DRV$16-OUTA)") (class "Default")
      (node (ref "C61") (pin "1") (pinfunction "1_1") (pintype "passive"))
      (node (ref "DRV$16") (pin "9") (pinfunction "OUTA_9") (pintype "bidirectional"))
    )
    (net (code "153") (name "Net-(DRV$16-OUTB)") (class "Default")
      (node (ref "C62") (pin "1") (pinfunction "1_1") (pintype "passive"))
      (node (ref "DRV$16") (pin "7") (pinfunction "OUTB_7") (pintype "bidirectional"))
    )
    (net (code "154") (name "QH*$1") (class "Default")
      (node (ref "IC1") (pin "9") (pinfunction "QH*_9") (pintype "tri_state"))
      (node (ref "IC2") (pin "14") (pinfunction "SER_14") (pintype "input"))
    )
    (net (code "155") (name "QH*$2") (class "Default")
      (node (ref "IC2") (pin "9") (pinfunction "QH*_9") (pintype "tri_state"))
      (node (ref "IC3") (pin "14") (pinfunction "SER_14") (pintype "input"))
    )
    (net (code "156") (name "QH*$3") (class "Default")
      (node (ref "IC3") (pin "9") (pinfunction "QH*_9") (pintype "tri_state"))
      (node (ref "IC4") (pin "14") (pinfunction "SER_14") (pintype "input"))
    )
    (net (code "157") (name "QH*$4") (class "Default")
      (node (ref "IC4") (pin "9") (pinfunction "QH*_9") (pintype "tri_state"))
      (node (ref "JP2") (pin "2") (pinfunction "2_2") (pintype "passive"))
    )
    (net (code "158") (name "RCK") (class "Default")
      (node (ref "IC1") (pin "12") (pinfunction "RCK_12") (pintype "input"))
      (node (ref "IC2") (pin "12") (pinfunction "RCK_12") (pintype "input"))
      (node (ref "IC3") (pin "12") (pinfunction "RCK_12") (pintype "input"))
      (node (ref "IC4") (pin "12") (pinfunction "RCK_12") (pintype "input"))
      (node (ref "JP1") (pin "4") (pinfunction "4_4") (pintype "passive"))
      (node (ref "JP2") (pin "4") (pinfunction "4_4") (pintype "passive"))
    )
    (net (code "159") (name "SCK") (class "Default")
      (node (ref "IC1") (pin "11") (pinfunction "SCK_11") (pintype "input"))
      (node (ref "IC2") (pin "11") (pinfunction "SCK_11") (pintype "input"))
      (node (ref "IC3") (pin "11") (pinfunction "SCK_11") (pintype "input"))
      (node (ref "IC4") (pin "11") (pinfunction "SCK_11") (pintype "input"))
      (node (ref "JP1") (pin "3") (pinfunction "3_3") (pintype "passive"))
      (node (ref "JP2") (pin "3") (pinfunction "3_3") (pintype "passive"))
    )
    (net (code "160") (name "SER") (class "Default")
      (node (ref "IC1") (pin "14") (pinfunction "SER_14") (pintype "input"))
      (node (ref "JP1") (pin "2") (pinfunction "2_2") (pintype "passive"))
    )
    (net (code "161") (name "VPP") (class "Default")
      (node (ref "C11") (pin "1") (pinfunction "1_1") (pintype "passive"))
      (node (ref "C15") (pin "1") (pinfunction "1_1") (pintype "passive"))
      (node (ref "C19") (pin "1") (pinfunction "1_1") (pintype "passive"))
      (node (ref "C23") (pin "1") (pinfunction "1_1") (pintype "passive"))
      (node (ref "C27") (pin "1") (pinfunction "1_1") (pintype "passive"))
      (node (ref "C3") (pin "1") (pinfunction "1_1") (pintype "passive"))
      (node (ref "C31") (pin "1") (pinfunction "1_1") (pintype "passive"))
      (node (ref "C35") (pin "1") (pinfunction "1_1") (pintype "passive"))
      (node (ref "C39") (pin "1") (pinfunction "1_1") (pintype "passive"))
      (node (ref "C43") (pin "1") (pinfunction "1_1") (pintype "passive"))
      (node (ref "C47") (pin "1") (pinfunction "1_1") (pintype "passive"))
      (node (ref "C51") (pin "1") (pinfunction "1_1") (pintype "passive"))
      (node (ref "C55") (pin "1") (pinfunction "1_1") (pintype "passive"))
      (node (ref "C59") (pin "1") (pinfunction "1_1") (pintype "passive"))
      (node (ref "C63") (pin "1") (pinfunction "1_1") (pintype "passive"))
      (node (ref "C7") (pin "1") (pinfunction "1_1") (pintype "passive"))
      (node (ref "CMOS$1") (pin "3") (pinfunction "SP_3") (pintype "bidirectional"))
      (node (ref "CMOS$10") (pin "3") (pinfunction "SP_3") (pintype "bidirectional"))
      (node (ref "CMOS$11") (pin "3") (pinfunction "SP_3") (pintype "bidirectional"))
      (node (ref "CMOS$12") (pin "3") (pinfunction "SP_3") (pintype "bidirectional"))
      (node (ref "CMOS$13") (pin "3") (pinfunction "SP_3") (pintype "bidirectional"))
      (node (ref "CMOS$14") (pin "3") (pinfunction "SP_3") (pintype "bidirectional"))
      (node (ref "CMOS$15") (pin "3") (pinfunction "SP_3") (pintype "bidirectional"))
      (node (ref "CMOS$16") (pin "3") (pinfunction "SP_3") (pintype "bidirectional"))
      (node (ref "CMOS$2") (pin "3") (pinfunction "SP_3") (pintype "bidirectional"))
      (node (ref "CMOS$3") (pin "3") (pinfunction "SP_3") (pintype "bidirectional"))
      (node (ref "CMOS$4") (pin "3") (pinfunction "SP_3") (pintype "bidirectional"))
      (node (ref "CMOS$5") (pin "3") (pinfunction "SP_3") (pintype "bidirectional"))
      (node (ref "CMOS$6") (pin "3") (pinfunction "SP_3") (pintype "bidirectional"))
      (node (ref "CMOS$7") (pin "3") (pinfunction "SP_3") (pintype "bidirectional"))
      (node (ref "CMOS$8") (pin "3") (pinfunction "SP_3") (pintype "bidirectional"))
      (node (ref "CMOS$9") (pin "3") (pinfunction "SP_3") (pintype "bidirectional"))
      (node (ref "JP1") (pin "1") (pinfunction "1_1") (pintype "passive"))
      (node (ref "JP2") (pin "1") (pinfunction "1_1") (pintype "passive"))
      (node (ref "R1") (pin "2") (pinfunction "2_2") (pintype "passive"))
      (node (ref "R11") (pin "2") (pinfunction "2_2") (pintype "passive"))
      (node (ref "R13") (pin "2") (pinfunction "2_2") (pintype "passive"))
      (node (ref "R15") (pin "2") (pinfunction "2_2") (pintype "passive"))
      (node (ref "R17") (pin "2") (pinfunction "2_2") (pintype "passive"))
      (node (ref "R19") (pin "2") (pinfunction "2_2") (pintype "passive"))
      (node (ref "R21") (pin "2") (pinfunction "2_2") (pintype "passive"))
      (node (ref "R23") (pin "2") (pinfunction "2_2") (pintype "passive"))
      (node (ref "R25") (pin "2") (pinfunction "2_2") (pintype "passive"))
      (node (ref "R27") (pin "2") (pinfunction "2_2") (pintype "passive"))
      (node (ref "R29") (pin "2") (pinfunction "2_2") (pintype "passive"))
      (node (ref "R3") (pin "2") (pinfunction "2_2") (pintype "passive"))
      (node (ref "R31") (pin "2") (pinfunction "2_2") (pintype "passive"))
      (node (ref "R5") (pin "2") (pinfunction "2_2") (pintype "passive"))
      (node (ref "R7") (pin "2") (pinfunction "2_2") (pintype "passive"))
      (node (ref "R9") (pin "2") (pinfunction "2_2") (pintype "passive"))
      (node (ref "ZD1") (pin "P$1") (pinfunction "K_P$1") (pintype "passive"))
      (node (ref "ZD11") (pin "P$1") (pinfunction "K_P$1") (pintype "passive"))
      (node (ref "ZD13") (pin "P$1") (pinfunction "K_P$1") (pintype "passive"))
      (node (ref "ZD15") (pin "P$1") (pinfunction "K_P$1") (pintype "passive"))
      (node (ref "ZD17") (pin "P$1") (pinfunction "K_P$1") (pintype "passive"))
      (node (ref "ZD19") (pin "P$1") (pinfunction "K_P$1") (pintype "passive"))
      (node (ref "ZD21") (pin "P$1") (pinfunction "K_P$1") (pintype "passive"))
      (node (ref "ZD23") (pin "P$1") (pinfunction "K_P$1") (pintype "passive"))
      (node (ref "ZD25") (pin "P$1") (pinfunction "K_P$1") (pintype "passive"))
      (node (ref "ZD27") (pin "P$1") (pinfunction "K_P$1") (pintype "passive"))
      (node (ref "ZD29") (pin "P$1") (pinfunction "K_P$1") (pintype "passive"))
      (node (ref "ZD3") (pin "P$1") (pinfunction "K_P$1") (pintype "passive"))
      (node (ref "ZD31") (pin "P$1") (pinfunction "K_P$1") (pintype "passive"))
      (node (ref "ZD5") (pin "P$1") (pinfunction "K_P$1") (pintype "passive"))
      (node (ref "ZD7") (pin "P$1") (pinfunction "K_P$1") (pintype "passive"))
      (node (ref "ZD9") (pin "P$1") (pinfunction "K_P$1") (pintype "passive"))
    )
  )
)
